# design.net
KiCad netlist of a schematic drawn in Altium Designer
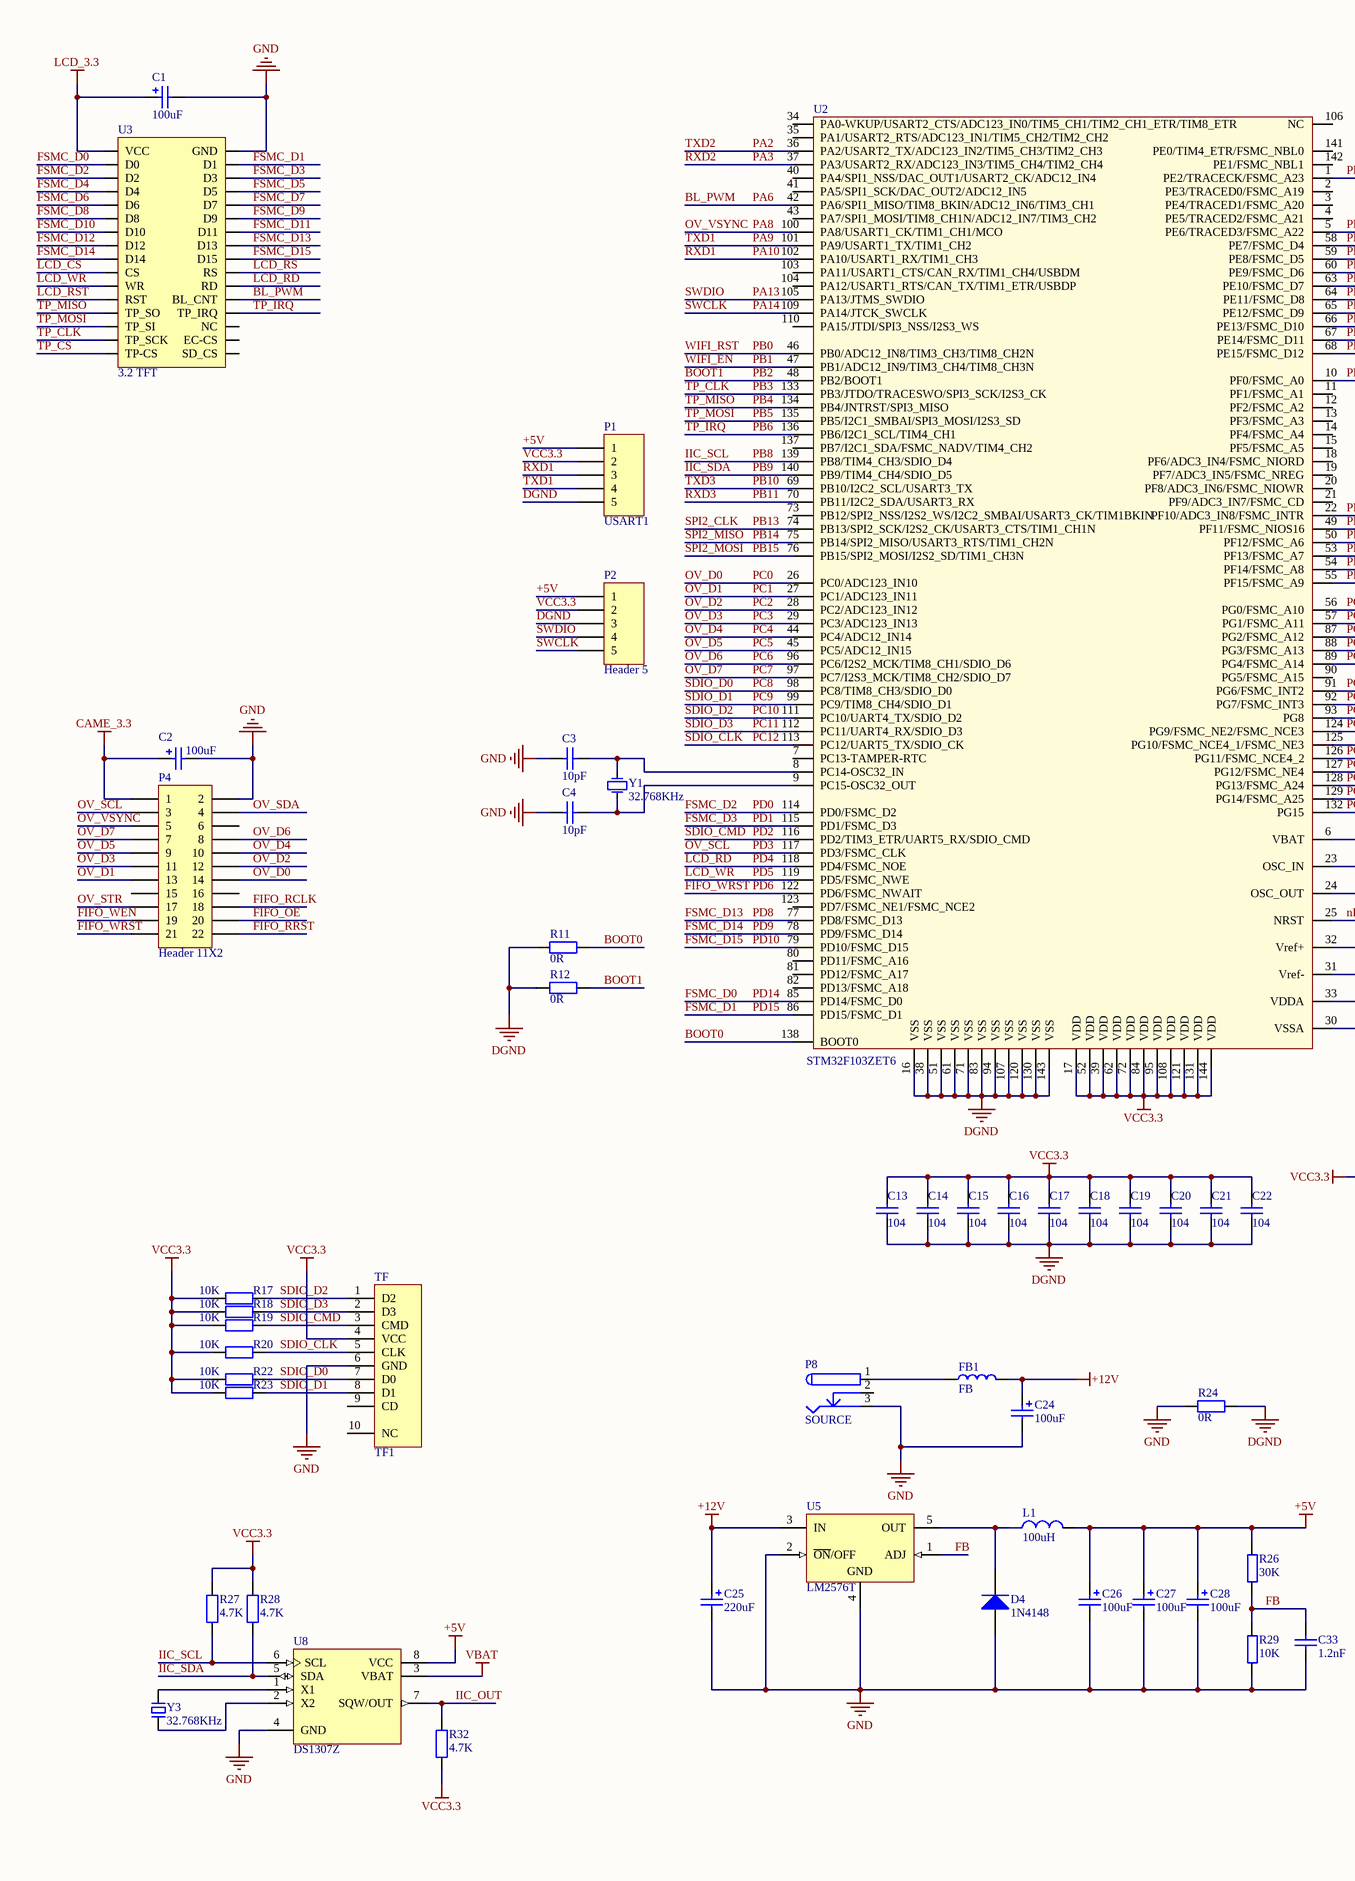
[diagram p0: 无线门禁系统.SchDoc, left]
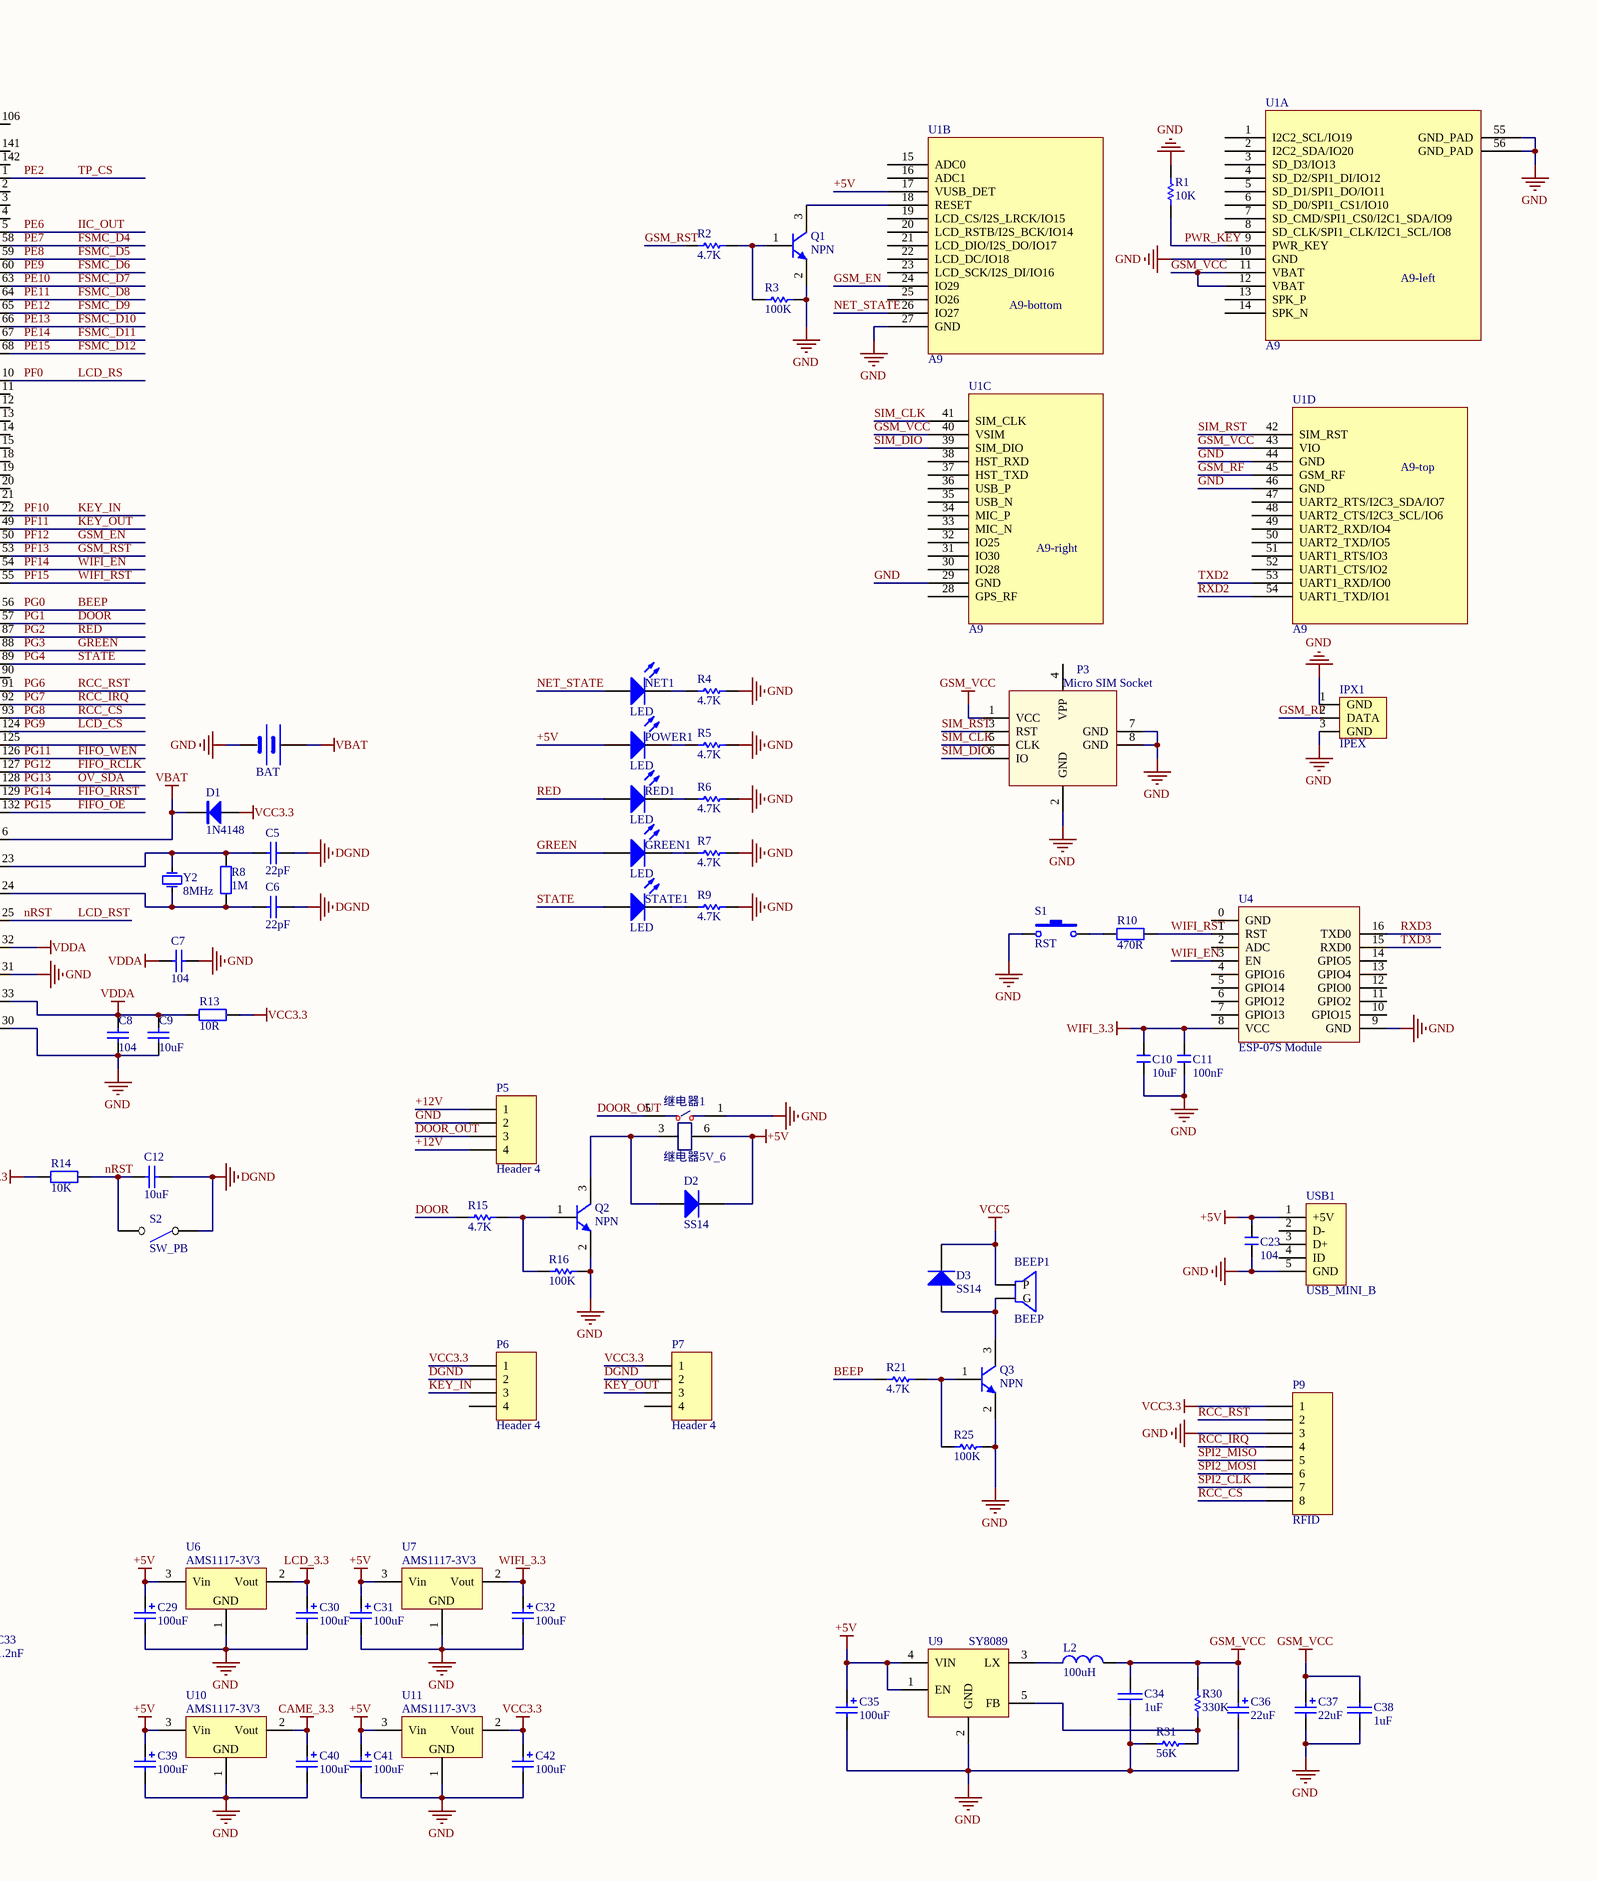
[diagram p1: 无线门禁系统.SchDoc, right]

(export (version "E")
  (design (tool "Eeschema 10.0.6"))
  (components
    (comp (ref "BAT")
      (value "BATT")
      (footprint "MyLib:纽扣电池座CR1220")
      (libsource (lib "Peace的集成库") (part "BAT"))
    )
    (comp (ref "BEEP1") (value "BEEP") (footprint "MyLib:BUZZER") (libsource (lib "门禁系统") (part "BEEP")))
    (comp (ref "C1")
      (value "100uF")
      (footprint "WiFi无线门禁_主机:CAP_TAN_B_3518")
      (description "Polarized Capacitor (Radial)")
      (fields
        (field (name "VOLTAGE") "16V")
        (field (name "Comment") "Cap Pol SMT D")
        (field (name "PUBLISHER") "Altium Limited")
      )
      (libsource (lib "MyLib") (part "Cap Pol SMT D"))
    )
    (comp (ref "C2")
      (value "100uF")
      (footprint "WiFi无线门禁_主机:CAP_TAN_B_3518")
      (description "Polarized Capacitor (Radial)")
      (fields
        (field (name "VOLTAGE") "16V")
        (field (name "Comment") "Cap Pol SMT D")
        (field (name "PUBLISHER") "Altium Limited")
      )
      (libsource (lib "MyLib") (part "Cap Pol SMT D"))
    )
    (comp (ref "C3")
      (value "10pF")
      (footprint "MyLib:0805_c")
      (description "Capacitor")
      (fields (field (name "Comment") "Cap1") (field (name "PUBLISHER") "Altium Limited"))
      (libsource (lib "Peace的集成库") (part "Cap1"))
    )
    (comp (ref "C4")
      (value "10pF")
      (footprint "MyLib:0805_c")
      (description "Capacitor")
      (fields (field (name "Comment") "Cap1") (field (name "PUBLISHER") "Altium Limited"))
      (libsource (lib "Peace的集成库") (part "Cap1"))
    )
    (comp (ref "C5")
      (value "22pF")
      (footprint "MyLib:0805_c")
      (description "Capacitor")
      (fields (field (name "Comment") "Cap1") (field (name "PUBLISHER") "Altium Limited"))
      (libsource (lib "Peace的集成库") (part "Cap1"))
    )
    (comp (ref "C6")
      (value "22pF")
      (footprint "MyLib:0805_c")
      (description "Capacitor")
      (fields (field (name "Comment") "Cap1") (field (name "PUBLISHER") "Altium Limited"))
      (libsource (lib "Peace的集成库") (part "Cap1"))
    )
    (comp (ref "C7")
      (value "104")
      (footprint "MyLib:0805_c")
      (description "Capacitor")
      (fields (field (name "Comment") "Cap1") (field (name "PUBLISHER") "Altium Limited"))
      (libsource (lib "Peace的集成库") (part "Cap1"))
    )
    (comp (ref "C8")
      (value "104")
      (footprint "MyLib:0805_c")
      (description "Capacitor")
      (fields (field (name "Comment") "Cap1") (field (name "PUBLISHER") "Altium Limited"))
      (libsource (lib "Peace的集成库") (part "Cap1"))
    )
    (comp (ref "C9")
      (value "10uF")
      (footprint "MyLib:0805_c")
      (description "Capacitor")
      (fields (field (name "Comment") "Cap1") (field (name "PUBLISHER") "Altium Limited"))
      (libsource (lib "Peace的集成库") (part "Cap1"))
    )
    (comp (ref "C10")
      (value "10uF")
      (footprint "MyLib:0805_c")
      (description "无极性贴片电容")
      (fields (field (name "版权归属") "源创客"))
      (libsource (lib "EEBANG_STM32F103ZET6") (part "C"))
    )
    (comp (ref "C11")
      (value "100nF")
      (footprint "MyLib:0805_c")
      (description "无极性贴片电容")
      (fields (field (name "版权归属") "源创客"))
      (libsource (lib "EEBANG_STM32F103ZET6") (part "C"))
    )
    (comp (ref "C12")
      (value "10uF")
      (footprint "MyLib:0805_c")
      (description "Capacitor")
      (fields (field (name "Comment") "Cap1") (field (name "PUBLISHER") "Altium Limited"))
      (libsource (lib "Peace的集成库") (part "Cap1"))
    )
    (comp (ref "C13")
      (value "104")
      (footprint "MyLib:0805_c")
      (description "Capacitor")
      (fields (field (name "Comment") "Cap1") (field (name "PUBLISHER") "Altium Limited"))
      (libsource (lib "Peace的集成库") (part "Cap1"))
    )
    (comp (ref "C14")
      (value "104")
      (footprint "MyLib:0805_c")
      (description "Capacitor")
      (fields (field (name "Comment") "Cap1") (field (name "PUBLISHER") "Altium Limited"))
      (libsource (lib "Peace的集成库") (part "Cap1"))
    )
    (comp (ref "C15")
      (value "104")
      (footprint "MyLib:0805_c")
      (description "Capacitor")
      (fields (field (name "Comment") "Cap1") (field (name "PUBLISHER") "Altium Limited"))
      (libsource (lib "Peace的集成库") (part "Cap1"))
    )
    (comp (ref "C16")
      (value "104")
      (footprint "MyLib:0805_c")
      (description "Capacitor")
      (fields (field (name "Comment") "Cap1") (field (name "PUBLISHER") "Altium Limited"))
      (libsource (lib "Peace的集成库") (part "Cap1"))
    )
    (comp (ref "C17")
      (value "104")
      (footprint "MyLib:0805_c")
      (description "Capacitor")
      (fields (field (name "Comment") "Cap1") (field (name "PUBLISHER") "Altium Limited"))
      (libsource (lib "Peace的集成库") (part "Cap1"))
    )
    (comp (ref "C18")
      (value "104")
      (footprint "MyLib:0805_c")
      (description "Capacitor")
      (fields (field (name "Comment") "Cap1") (field (name "PUBLISHER") "Altium Limited"))
      (libsource (lib "Peace的集成库") (part "Cap1"))
    )
    (comp (ref "C19")
      (value "104")
      (footprint "MyLib:0805_c")
      (description "Capacitor")
      (fields (field (name "Comment") "Cap1") (field (name "PUBLISHER") "Altium Limited"))
      (libsource (lib "Peace的集成库") (part "Cap1"))
    )
    (comp (ref "C20")
      (value "104")
      (footprint "MyLib:0805_c")
      (description "Capacitor")
      (fields (field (name "Comment") "Cap1") (field (name "PUBLISHER") "Altium Limited"))
      (libsource (lib "Peace的集成库") (part "Cap1"))
    )
    (comp (ref "C21")
      (value "104")
      (footprint "MyLib:0805_c")
      (description "Capacitor")
      (fields (field (name "Comment") "Cap1") (field (name "PUBLISHER") "Altium Limited"))
      (libsource (lib "Peace的集成库") (part "Cap1"))
    )
    (comp (ref "C22")
      (value "104")
      (footprint "MyLib:0805_c")
      (description "Capacitor")
      (fields (field (name "Comment") "Cap1") (field (name "PUBLISHER") "Altium Limited"))
      (libsource (lib "Peace的集成库") (part "Cap1"))
    )
    (comp (ref "C23")
      (value "104")
      (footprint "MyLib:0805_c")
      (description "无极性贴片电容")
      (fields (field (name "版权归属") "源创客"))
      (libsource (lib "EEBANG_STM32F103ZET6") (part "C"))
    )
    (comp (ref "C24")
      (value "100uF")
      (footprint "WiFi无线门禁_主机:CAP_TAN_B_3518")
      (description "Polarized Capacitor (Radial)")
      (fields
        (field (name "VOLTAGE") "16V")
        (field (name "Comment") "Cap Tan A")
        (field (name "PUBLISHER") "Altium Limited")
      )
      (libsource (lib "MyLib") (part "Cap Tan A"))
    )
    (comp (ref "C25")
      (value "220uF")
      (footprint "WiFi无线门禁_主机:CAP_TAN_B_3518")
      (description "Polarized Capacitor (Radial)")
      (fields (field (name "Comment") "Cap Electrolytic") (field (name "PUBLISHER") "Altium Limited"))
      (libsource (lib "MyLib") (part "Cap Electrolytic"))
    )
    (comp (ref "C26")
      (value "100uF")
      (footprint "WiFi无线门禁_主机:CAP_TAN_B_3518")
      (description "Polarized Capacitor (Radial)")
      (fields
        (field (name "VOLTAGE") "16V")
        (field (name "Comment") "Cap Tan A")
        (field (name "PUBLISHER") "Altium Limited")
      )
      (libsource (lib "MyLib") (part "Cap Tan A"))
    )
    (comp (ref "C27")
      (value "100uF")
      (footprint "WiFi无线门禁_主机:CAP_TAN_B_3518")
      (description "Polarized Capacitor (Radial)")
      (fields
        (field (name "VOLTAGE") "16V")
        (field (name "Comment") "Cap Tan A")
        (field (name "PUBLISHER") "Altium Limited")
      )
      (libsource (lib "MyLib") (part "Cap Tan A"))
    )
    (comp (ref "C28")
      (value "100uF")
      (footprint "WiFi无线门禁_主机:CAP_TAN_B_3518")
      (description "Polarized Capacitor (Radial)")
      (fields
        (field (name "VOLTAGE") "16V")
        (field (name "Comment") "Cap Tan A")
        (field (name "PUBLISHER") "Altium Limited")
      )
      (libsource (lib "MyLib") (part "Cap Tan A"))
    )
    (comp (ref "C29")
      (value "100uF")
      (footprint "WiFi无线门禁_主机:CAP_TAN_B_3518")
      (description "Polarized Capacitor (Radial)")
      (fields
        (field (name "VOLTAGE") "16V")
        (field (name "Comment") "Cap Pol SMT D")
        (field (name "PUBLISHER") "Altium Limited")
      )
      (libsource (lib "MyLib") (part "Cap Pol SMT D"))
    )
    (comp (ref "C30")
      (value "100uF")
      (footprint "WiFi无线门禁_主机:CAP_TAN_B_3518")
      (description "Polarized Capacitor (Radial)")
      (fields
        (field (name "VOLTAGE") "16V")
        (field (name "Comment") "Cap Pol SMT D")
        (field (name "PUBLISHER") "Altium Limited")
      )
      (libsource (lib "MyLib") (part "Cap Pol SMT D"))
    )
    (comp (ref "C31")
      (value "100uF")
      (footprint "WiFi无线门禁_主机:CAP_TAN_B_3518")
      (description "Polarized Capacitor (Radial)")
      (fields
        (field (name "VOLTAGE") "16V")
        (field (name "Comment") "Cap Pol SMT D")
        (field (name "PUBLISHER") "Altium Limited")
      )
      (libsource (lib "MyLib") (part "Cap Pol SMT D"))
    )
    (comp (ref "C32")
      (value "100uF")
      (footprint "WiFi无线门禁_主机:CAP_TAN_B_3518")
      (description "Polarized Capacitor (Radial)")
      (fields
        (field (name "VOLTAGE") "16V")
        (field (name "Comment") "Cap Pol SMT D")
        (field (name "PUBLISHER") "Altium Limited")
      )
      (libsource (lib "MyLib") (part "Cap Pol SMT D"))
    )
    (comp (ref "C33")
      (value "1.2nF")
      (footprint "MyLib:0805_c")
      (description "Polarized Capacitor (Radial)")
      (fields (field (name "Comment") "Cap Chip 0805") (field (name "PUBLISHER") "Altium Limited"))
      (libsource (lib "MyLib") (part "Cap Chip 0805"))
    )
    (comp (ref "C34") (value "1uF") (footprint "MyLib:0805_c") (libsource (lib "MyLib") (part "CAP")))
    (comp (ref "C35")
      (value "100uF")
      (footprint "WiFi无线门禁_主机:CAP_TAN_B_3518")
      (description "Polarized Capacitor (Radial)")
      (fields
        (field (name "VOLTAGE") "16V")
        (field (name "Comment") "Cap Pol SMT D")
        (field (name "PUBLISHER") "Altium Limited")
      )
      (libsource (lib "MyLib") (part "Cap Pol SMT D"))
    )
    (comp (ref "C36")
      (value "22uF")
      (footprint "WiFi无线门禁_主机:CAP_TAN_B_3518")
      (description "Polarized Capacitor (Radial)")
      (fields
        (field (name "VOLTAGE") "16V")
        (field (name "Comment") "Cap Pol SMT D")
        (field (name "PUBLISHER") "Altium Limited")
      )
      (libsource (lib "MyLib") (part "Cap Pol SMT D"))
    )
    (comp (ref "C37")
      (value "22uF")
      (footprint "WiFi无线门禁_主机:CAP_TAN_B_3518")
      (description "Polarized Capacitor (Radial)")
      (fields
        (field (name "VOLTAGE") "16V")
        (field (name "Comment") "Cap Pol SMT D")
        (field (name "PUBLISHER") "Altium Limited")
      )
      (libsource (lib "MyLib") (part "Cap Pol SMT D"))
    )
    (comp (ref "C38") (value "1uF") (footprint "MyLib:0805_c") (libsource (lib "MyLib") (part "CAP")))
    (comp (ref "C39")
      (value "100uF")
      (footprint "WiFi无线门禁_主机:CAP_TAN_B_3518")
      (description "Polarized Capacitor (Radial)")
      (fields
        (field (name "VOLTAGE") "16V")
        (field (name "Comment") "Cap Pol SMT D")
        (field (name "PUBLISHER") "Altium Limited")
      )
      (libsource (lib "MyLib") (part "Cap Pol SMT D"))
    )
    (comp (ref "C40")
      (value "100uF")
      (footprint "WiFi无线门禁_主机:CAP_TAN_B_3518")
      (description "Polarized Capacitor (Radial)")
      (fields
        (field (name "VOLTAGE") "16V")
        (field (name "Comment") "Cap Pol SMT D")
        (field (name "PUBLISHER") "Altium Limited")
      )
      (libsource (lib "MyLib") (part "Cap Pol SMT D"))
    )
    (comp (ref "C41")
      (value "100uF")
      (footprint "WiFi无线门禁_主机:CAP_TAN_B_3518")
      (description "Polarized Capacitor (Radial)")
      (fields
        (field (name "VOLTAGE") "16V")
        (field (name "Comment") "Cap Pol SMT D")
        (field (name "PUBLISHER") "Altium Limited")
      )
      (libsource (lib "MyLib") (part "Cap Pol SMT D"))
    )
    (comp (ref "C42")
      (value "100uF")
      (footprint "WiFi无线门禁_主机:CAP_TAN_B_3518")
      (description "Polarized Capacitor (Radial)")
      (fields
        (field (name "VOLTAGE") "16V")
        (field (name "Comment") "Cap Pol SMT D")
        (field (name "PUBLISHER") "Altium Limited")
      )
      (libsource (lib "MyLib") (part "Cap Pol SMT D"))
    )
    (comp (ref "D1")
      (value "1N4148")
      (footprint "二极管:DIODE SMC")
      (description "高速开关二极管")
      (fields (field (name "版权归属") "源创客"))
      (libsource (lib "EEBANG_STM32F103ZET6") (part "1N4148"))
    )
    (comp (ref "D2")
      (value "SS14")
      (footprint "二极管:DIODE SMC")
      (description "High Conductance Fast Diode")
      (fields (field (name "PUBLISHER") "Altium Limited"))
      (libsource (lib "My Footprint") (part "1N4148"))
    )
    (comp (ref "D3")
      (value "SS14")
      (footprint "二极管:DIODE SMC")
      (description "High Conductance Fast Diode")
      (fields (field (name "PUBLISHER") "Altium Limited"))
      (libsource (lib "My Footprint") (part "1N4148"))
    )
    (comp (ref "D4")
      (value "1N4148")
      (footprint "二极管:DIODE SMC")
      (description "3 Amp Medium Power Silicon Rectifier Diode")
      (fields (field (name "PUBLISHER") "Altium Limited"))
      (libsource (lib "MyLib") (part "Diode"))
    )
    (comp (ref "FB1")
      (value "FB")
      (footprint "MyLib:FU 1206")
      (description "磁珠")
      (libsource (lib "My Footprint") (part "FB"))
    )
    (comp (ref "GREEN1") (value "LED") (footprint "MyLib:0805_LED") (libsource (lib "MyLib") (part "LED")))
    (comp (ref "IPX1")
      (value "IPEX")
      (footprint "IPEX")
      (description "IPEX座")
      (libsource (lib "PCB_Project1") (part "IPEX"))
    )
    (comp (ref "L1") (value "100uH") (footprint "MyLib:L_3") (libsource (lib "MyLib") (part "inductance")))
    (comp (ref "L2") (value "100uH") (footprint "MyLib:L_3") (libsource (lib "MyLib") (part "inductance")))
    (comp (ref "NET1") (value "LED") (footprint "MyLib:0805_LED") (libsource (lib "MyLib") (part "LED")))
    (comp (ref "P1")
      (value "USART1")
      (footprint "MyLib:HX2.54-5")
      (description "Header, 5-Pin")
      (fields (field (name "PUBLISHER") "Altium Limited"))
      (libsource (lib "MyLib") (part "Header 5"))
    )
    (comp (ref "P2")
      (value "Header 5")
      (footprint "MyLib:HX2.54-5")
      (description "Header, 5-Pin")
      (fields (field (name "PUBLISHER") "Altium Limited"))
      (libsource (lib "MyLib") (part "Header 5"))
    )
    (comp (ref "P3")
      (value "Micro SIM Socket")
      (footprint "PCB_Project1:SIM_micro")
      (libsource (lib "MyLib") (part "Micro SIM"))
    )
    (comp (ref "P4")
      (value "Header 11X2")
      (footprint "HDR2X11")
      (description "Header, 11-Pin, Dual row")
      (fields (field (name "PUBLISHER") "Altium Limited"))
      (libsource (lib "MyLib") (part "Header 11X2"))
    )
    (comp (ref "P5")
      (value "Header 4")
      (footprint "MyLib:HX2.54-4")
      (description "Header, 4-Pin")
      (fields (field (name "PUBLISHER") "Altium Limited"))
      (libsource (lib "MyLib") (part "Header 4"))
    )
    (comp (ref "P6")
      (value "Header 4")
      (footprint "MyLib:HX2.54-4")
      (description "Header, 4-Pin")
      (fields (field (name "PUBLISHER") "Altium Limited"))
      (libsource (lib "MyLib") (part "Header 4"))
    )
    (comp (ref "P7")
      (value "Header 4")
      (footprint "MyLib:HX2.54-4")
      (description "Header, 4-Pin")
      (fields (field (name "PUBLISHER") "Altium Limited"))
      (libsource (lib "MyLib") (part "Header 4"))
    )
    (comp (ref "P8")
      (value "SOURCE")
      (footprint "MyLib:source")
      (fields (field (name "PUBLISHER") "Altium Limited"))
      (libsource (lib "My Footprint") (part "SOURCE"))
    )
    (comp (ref "P9")
      (value "RFID")
      (footprint "MyLib:HX2.54-8")
      (description "Header, 8-Pin")
      (fields (field (name "PUBLISHER") "Altium Limited"))
      (libsource (lib "MyLib") (part "Header 8"))
    )
    (comp (ref "POWER1") (value "LED") (footprint "MyLib:0805_LED") (libsource (lib "MyLib") (part "LED")))
    (comp (ref "Q1")
      (value "NPN")
      (footprint "MyLib:SOT-23-3")
      (description "贴片")
      (libsource (lib "My Footprint") (part "NPN2"))
    )
    (comp (ref "Q2")
      (value "NPN")
      (footprint "MyLib:SOT-23-3")
      (description "贴片")
      (libsource (lib "My Footprint") (part "NPN2"))
    )
    (comp (ref "Q3")
      (value "NPN")
      (footprint "MyLib:SOT-23-3")
      (description "贴片")
      (libsource (lib "My Footprint") (part "NPN2"))
    )
    (comp (ref "R1")
      (value "10K")
      (footprint "0805_r")
      (description "Resistor")
      (fields (field (name "PUBLISHER") "Altium Limited"))
      (libsource (lib "My Footprint") (part "RES"))
    )
    (comp (ref "R2")
      (value "4.7K")
      (footprint "0805_r")
      (description "Resistor")
      (fields (field (name "PUBLISHER") "Altium Limited"))
      (libsource (lib "My Footprint") (part "RES"))
    )
    (comp (ref "R3")
      (value "100K")
      (footprint "0805_r")
      (description "Resistor")
      (fields (field (name "PUBLISHER") "Altium Limited"))
      (libsource (lib "My Footprint") (part "RES"))
    )
    (comp (ref "R4")
      (value "4.7K")
      (footprint "0805_r")
      (description "Resistor")
      (fields (field (name "PUBLISHER") "Altium Limited"))
      (libsource (lib "My Footprint") (part "RES"))
    )
    (comp (ref "R5")
      (value "4.7K")
      (footprint "0805_r")
      (description "Resistor")
      (fields (field (name "PUBLISHER") "Altium Limited"))
      (libsource (lib "My Footprint") (part "RES"))
    )
    (comp (ref "R6")
      (value "4.7K")
      (footprint "0805_r")
      (description "Resistor")
      (fields (field (name "PUBLISHER") "Altium Limited"))
      (libsource (lib "My Footprint") (part "RES"))
    )
    (comp (ref "R7")
      (value "4.7K")
      (footprint "0805_r")
      (description "Resistor")
      (fields (field (name "PUBLISHER") "Altium Limited"))
      (libsource (lib "My Footprint") (part "RES"))
    )
    (comp (ref "R8")
      (value "1M")
      (footprint "MyLib:0805_r")
      (description "Resistor")
      (fields (field (name "Comment") "Res1") (field (name "PUBLISHER") "Altium Limited"))
      (libsource (lib "") (part "Res1_2"))
    )
    (comp (ref "R9")
      (value "4.7K")
      (footprint "0805_r")
      (description "Resistor")
      (fields (field (name "PUBLISHER") "Altium Limited"))
      (libsource (lib "My Footprint") (part "RES"))
    )
    (comp (ref "R10")
      (value "470R")
      (footprint "MyLib:0805_r")
      (description "Resistor")
      (fields (field (name "Comment") "Res1") (field (name "PUBLISHER") "Altium Limited"))
      (libsource (lib "Peace的集成库") (part "Res1"))
    )
    (comp (ref "R11")
      (value "0R")
      (footprint "MyLib:0805_r")
      (description "Resistor")
      (fields (field (name "Comment") "Res1") (field (name "PUBLISHER") "Altium Limited"))
      (libsource (lib "Peace的集成库") (part "Res1"))
    )
    (comp (ref "R12")
      (value "0R")
      (footprint "MyLib:0805_r")
      (description "Resistor")
      (fields (field (name "Comment") "Res1") (field (name "PUBLISHER") "Altium Limited"))
      (libsource (lib "Peace的集成库") (part "Res1"))
    )
    (comp (ref "R13")
      (value "10R")
      (footprint "MyLib:0805_r")
      (description "Resistor")
      (fields (field (name "Comment") "Res1") (field (name "PUBLISHER") "Altium Limited"))
      (libsource (lib "") (part "Res1_1"))
    )
    (comp (ref "R14")
      (value "10K")
      (footprint "MyLib:0805_r")
      (description "Resistor")
      (fields (field (name "Comment") "Res1") (field (name "PUBLISHER") "Altium Limited"))
      (libsource (lib "Peace的集成库") (part "Res1"))
    )
    (comp (ref "R15")
      (value "4.7K")
      (footprint "0805_r")
      (description "Resistor")
      (fields (field (name "PUBLISHER") "Altium Limited"))
      (libsource (lib "My Footprint") (part "RES"))
    )
    (comp (ref "R16")
      (value "100K")
      (footprint "0805_r")
      (description "Resistor")
      (fields (field (name "PUBLISHER") "Altium Limited"))
      (libsource (lib "My Footprint") (part "RES"))
    )
    (comp (ref "R17")
      (value "10K")
      (footprint "0805_r")
      (description "贴片电阻")
      (fields (field (name "版权归属") "源创客"))
      (libsource (lib "EEBANG_STM32F103ZET6") (part "R"))
    )
    (comp (ref "R18")
      (value "10K")
      (footprint "0805_r")
      (description "贴片电阻")
      (fields (field (name "版权归属") "源创客"))
      (libsource (lib "EEBANG_STM32F103ZET6") (part "R"))
    )
    (comp (ref "R19")
      (value "10K")
      (footprint "0805_r")
      (description "贴片电阻")
      (fields (field (name "版权归属") "源创客"))
      (libsource (lib "EEBANG_STM32F103ZET6") (part "R"))
    )
    (comp (ref "R20")
      (value "10K")
      (footprint "0805_r")
      (description "贴片电阻")
      (fields (field (name "版权归属") "源创客"))
      (libsource (lib "EEBANG_STM32F103ZET6") (part "R"))
    )
    (comp (ref "R21")
      (value "4.7K")
      (footprint "0805_r")
      (description "Resistor")
      (fields (field (name "PUBLISHER") "Altium Limited"))
      (libsource (lib "My Footprint") (part "RES"))
    )
    (comp (ref "R22")
      (value "10K")
      (footprint "0805_r")
      (description "贴片电阻")
      (fields (field (name "版权归属") "源创客"))
      (libsource (lib "EEBANG_STM32F103ZET6") (part "R"))
    )
    (comp (ref "R23")
      (value "10K")
      (footprint "0805_r")
      (description "贴片电阻")
      (fields (field (name "版权归属") "源创客"))
      (libsource (lib "EEBANG_STM32F103ZET6") (part "R"))
    )
    (comp (ref "R24")
      (value "0R")
      (footprint "MyLib:0805_r")
      (description "Resistor")
      (fields (field (name "Comment") "Res1") (field (name "PUBLISHER") "Altium Limited"))
      (libsource (lib "Peace的集成库") (part "Res1"))
    )
    (comp (ref "R25")
      (value "100K")
      (footprint "0805_r")
      (description "Resistor")
      (fields (field (name "PUBLISHER") "Altium Limited"))
      (libsource (lib "My Footprint") (part "RES"))
    )
    (comp (ref "R26") (value "30K") (footprint "MyLib:0805_r") (libsource (lib "MyLib") (part "RES3")))
    (comp (ref "R27")
      (value "4.7K")
      (footprint "0805_r")
      (description "贴片电阻")
      (fields (field (name "版权归属") "源创客"))
      (libsource (lib "EEBANG_STM32F103ZET6") (part "R"))
    )
    (comp (ref "R28")
      (value "4.7K")
      (footprint "0805_r")
      (description "贴片电阻")
      (fields (field (name "版权归属") "源创客"))
      (libsource (lib "EEBANG_STM32F103ZET6") (part "R"))
    )
    (comp (ref "R29") (value "10K") (footprint "0805_r") (libsource (lib "MyLib") (part "RES3")))
    (comp (ref "R30")
      (value "330K")
      (footprint "0805_r")
      (description "Resistor")
      (fields (field (name "PUBLISHER") "Altium Limited"))
      (libsource (lib "My Footprint") (part "RES"))
    )
    (comp (ref "R31")
      (value "56K")
      (footprint "0805_r")
      (description "Resistor")
      (fields (field (name "PUBLISHER") "Altium Limited"))
      (libsource (lib "My Footprint") (part "RES"))
    )
    (comp (ref "R32")
      (value "4.7K")
      (footprint "0805_r")
      (description "贴片电阻")
      (fields (field (name "版权归属") "源创客"))
      (libsource (lib "EEBANG_STM32F103ZET6") (part "R"))
    )
    (comp (ref "RED1") (value "LED") (footprint "MyLib:0805_LED") (libsource (lib "MyLib") (part "LED")))
    (comp (ref "S1")
      (value "RST")
      (footprint "KEY_2")
      (description "Switch")
      (fields (field (name "PUBLISHER") "Altium Limited"))
      (libsource (lib "Peace的集成库") (part "SW-PB"))
    )
    (comp (ref "S2") (value "SW_PB") (footprint "MyLib:KEY_2") (libsource (lib "MyLib") (part "单刀开关")))
    (comp (ref "STATE1") (value "LED") (footprint "MyLib:0805_LED") (libsource (lib "MyLib") (part "LED")))
    (comp (ref "TF1") (value "TF") (footprint "TF-2") (libsource (lib "WiFi无线门禁_主机") (part "TF2")))
    (comp (ref "U1") (value "A9") (footprint "A9") (libsource (lib "A9") (part "A9")))
    (comp (ref "U2")
      (value "STM32F103ZET6")
      (footprint "MyLib:TQFP144_L")
      (libsource (lib "EEBANG_STM32F103ZET6") (part "STM32F103ZET6"))
    )
    (comp (ref "U3") (value "3.2 TFT") (footprint "LCD3.2") (libsource (lib "WiFi无线门禁_主机") (part "LCD3.2")))
    (comp (ref "U4")
      (value "ESP-07S Module")
      (footprint "ESP-07S Module")
      (libsource (lib "ESP-07S Module") (part "ESP-07S Module"))
    )
    (comp (ref "U5")
      (value "LM2576T")
      (footprint "MyLib:TO-263-5")
      (description "Negative Low Dropout Adjustable Regulator")
      (fields
        (field (name "PARTNUMBER") "LM2991T")
        (field (name "MANUFACTURER") "National Semiconductor")
        (field (name "PUBLISHER") "Altium Limited")
      )
      (libsource (lib "MyLib") (part "LM2576T"))
    )
    (comp (ref "U6")
      (value "AMS1117-3V3")
      (footprint "MyLib:SOT-223")
      (description "三端稳压芯片")
      (fields (field (name "版权归属") "源创客"))
      (libsource (lib "EEBANG_STM32F103ZET6") (part "AMS1117"))
    )
    (comp (ref "U7")
      (value "AMS1117-3V3")
      (footprint "MyLib:SOT-223")
      (description "三端稳压芯片")
      (fields (field (name "版权归属") "源创客"))
      (libsource (lib "EEBANG_STM32F103ZET6") (part "AMS1117"))
    )
    (comp (ref "U8")
      (value "DS1307Z")
      (footprint "SOIC8_L")
      (description "64 X 8 Serial Real-Time Clock")
      (fields (field (name "PUBLISHER") "Altium Limited"))
      (libsource (lib "WiFi无线门禁_主机") (part "DS1307Z"))
    )
    (comp (ref "U9") (value "SY8089") (footprint "MyLib:SOP-5N") (libsource (lib "MyLib") (part "RT8059")))
    (comp (ref "U10")
      (value "AMS1117-3V3")
      (footprint "MyLib:SOT-223")
      (description "三端稳压芯片")
      (fields (field (name "版权归属") "源创客"))
      (libsource (lib "EEBANG_STM32F103ZET6") (part "AMS1117"))
    )
    (comp (ref "U11")
      (value "AMS1117-3V3")
      (footprint "MyLib:SOT-223")
      (description "三端稳压芯片")
      (fields (field (name "版权归属") "源创客"))
      (libsource (lib "EEBANG_STM32F103ZET6") (part "AMS1117"))
    )
    (comp (ref "USB1")
      (value "USB_MINI_B")
      (footprint "USB-MICRO_B")
      (description "微型USB母座")
      (fields (field (name "版权归属") "源创客"))
      (libsource (lib "EEBANG_STM32F103ZET6") (part "USB-5P"))
    )
    (comp (ref "Y1")
      (value "32.768KHz")
      (footprint "MyLib:XTAL-2")
      (description "Crystal Oscillator")
      (fields (field (name "PUBLISHER") "Altium Limited"))
      (libsource (lib "Peace的集成库") (part "XTAL"))
    )
    (comp (ref "Y2")
      (value "8MHz")
      (footprint "EEBANG_STM32F103ZET6:XTAL-49S SMD - L")
      (description "Crystal Oscillator")
      (fields (field (name "PUBLISHER") "Altium Limited"))
      (libsource (lib "Peace的集成库") (part "XTAL"))
    )
    (comp (ref "Y3")
      (value "32.768KHz")
      (footprint "XTAL-2")
      (description "2脚晶振")
      (fields (field (name "版权归属") "源创客"))
      (libsource (lib "EEBANG_STM32F103ZET6") (part "XTAL-2"))
    )
    (comp (ref "继电器1") (value "继电器5V_6") (footprint "门禁系统:继电器5V_6") (libsource (lib "门禁系统") (part "继电器5V_6")))
  )
  (nets
    (net (code "1") (name "+5V") (class "Default")
      (node (ref "C23") (pin "2") (pinfunction "2_2") (pintype "passive"))
      (node (ref "C26") (pin "2") (pinfunction "1_2") (pintype "passive"))
      (node (ref "C27") (pin "2") (pinfunction "1_2") (pintype "passive"))
      (node (ref "C28") (pin "2") (pinfunction "1_2") (pintype "passive"))
      (node (ref "C29") (pin "1") (pinfunction "1_1") (pintype "passive"))
      (node (ref "C31") (pin "1") (pinfunction "1_1") (pintype "passive"))
      (node (ref "C35") (pin "1") (pinfunction "1_1") (pintype "passive"))
      (node (ref "C39") (pin "1") (pinfunction "1_1") (pintype "passive"))
      (node (ref "C41") (pin "1") (pinfunction "1_1") (pintype "passive"))
      (node (ref "D2") (pin "2") (pinfunction "K_2") (pintype "passive"))
      (node (ref "L1") (pin "1") (pinfunction "1_1") (pintype "passive"))
      (node (ref "P1") (pin "1") (pinfunction "1_1") (pintype "passive"))
      (node (ref "P2") (pin "1") (pinfunction "1_1") (pintype "passive"))
      (node (ref "POWER1") (pin "1") (pinfunction "A_1") (pintype "passive"))
      (node (ref "R26") (pin "2") (pintype "passive"))
      (node (ref "U1") (pin "17") (pinfunction "VUSB_DET_17") (pintype "passive"))
      (node (ref "U10") (pin "3") (pinfunction "Vin_3") (pintype "passive"))
      (node (ref "U11") (pin "3") (pinfunction "Vin_3") (pintype "passive"))
      (node (ref "U6") (pin "3") (pinfunction "Vin_3") (pintype "passive"))
      (node (ref "U7") (pin "3") (pinfunction "Vin_3") (pintype "passive"))
      (node (ref "U8") (pin "8") (pinfunction "VCC_8") (pintype "power_in"))
      (node (ref "U9") (pin "1") (pinfunction "EN_1") (pintype "passive"))
      (node (ref "U9") (pin "4") (pinfunction "VIN_4") (pintype "passive"))
      (node (ref "USB1") (pin "1") (pinfunction "+5V_1") (pintype "passive"))
      (node (ref "继电器1") (pin "6") (pinfunction "FLA_6") (pintype "passive"))
    )
    (net (code "2") (name "+12V") (class "Default")
      (node (ref "C24") (pin "2") (pinfunction "1_2") (pintype "passive"))
      (node (ref "C25") (pin "1") (pinfunction "1_1") (pintype "passive"))
      (node (ref "FB1") (pin "2") (pinfunction "2_2") (pintype "passive"))
      (node (ref "P5") (pin "1") (pinfunction "1_1") (pintype "passive"))
      (node (ref "P5") (pin "4") (pinfunction "4_4") (pintype "passive"))
      (node (ref "U5") (pin "3") (pinfunction "IN_3") (pintype "power_in"))
    )
    (net (code "3") (name "/BEEP") (class "Default")
      (node (ref "R21") (pin "1") (pinfunction "1_1") (pintype "passive"))
      (node (ref "U2") (pin "56") (pinfunction "PG0/FSMC_A10_56") (pintype "passive"))
    )
    (net (code "4") (name "/BL_PWM") (class "Default")
      (node (ref "U2") (pin "42") (pinfunction "PA6/SPI1_MISO/TIM8_BKIN/ADC12_IN6/TIM3_CH1_42") (pintype "passive"))
      (node (ref "U3") (pin "24") (pinfunction "BL_CNT_24") (pintype "passive"))
    )
    (net (code "5") (name "/BOOT0") (class "Default")
      (node (ref "R11") (pin "1") (pinfunction "1_1") (pintype "passive"))
      (node (ref "U2") (pin "138") (pinfunction "BOOT0_138") (pintype "passive"))
    )
    (net (code "6") (name "/BOOT1") (class "Default")
      (node (ref "R12") (pin "1") (pinfunction "1_1") (pintype "passive"))
      (node (ref "U2") (pin "48") (pinfunction "PB2/BOOT1_48") (pintype "passive"))
    )
    (net (code "7") (name "/DOOR") (class "Default")
      (node (ref "R15") (pin "1") (pinfunction "1_1") (pintype "passive"))
      (node (ref "U2") (pin "57") (pinfunction "PG1/FSMC_A11_57") (pintype "passive"))
    )
    (net (code "8") (name "/DOOR_OUT") (class "Default")
      (node (ref "P5") (pin "3") (pinfunction "3_3") (pintype "passive"))
      (node (ref "继电器1") (pin "5") (pinfunction "FLA_5") (pintype "passive"))
    )
    (net (code "9") (name "/FB") (class "Default")
      (node (ref "C33") (pin "2") (pinfunction "2_2") (pintype "passive"))
      (node (ref "R26") (pin "1") (pintype "passive"))
      (node (ref "R29") (pin "2") (pintype "passive"))
      (node (ref "U5") (pin "1") (pinfunction "ADJ_1") (pintype "input"))
    )
    (net (code "10") (name "/FIFO_OE") (class "Default")
      (node (ref "P4") (pin "20") (pinfunction "20_20") (pintype "passive"))
      (node (ref "U2") (pin "132") (pinfunction "PG15_132") (pintype "passive"))
    )
    (net (code "11") (name "/FIFO_RCLK") (class "Default")
      (node (ref "P4") (pin "18") (pinfunction "18_18") (pintype "passive"))
      (node (ref "U2") (pin "127") (pinfunction "PG12/FSMC_NE4_127") (pintype "passive"))
    )
    (net (code "12") (name "/FIFO_RRST") (class "Default")
      (node (ref "P4") (pin "22") (pinfunction "22_22") (pintype "passive"))
      (node (ref "U2") (pin "129") (pinfunction "PG14/FSMC_A25_129") (pintype "passive"))
    )
    (net (code "13") (name "/FIFO_WEN") (class "Default")
      (node (ref "P4") (pin "19") (pinfunction "19_19") (pintype "passive"))
      (node (ref "U2") (pin "126") (pinfunction "PG11/FSMC_NCE4_2_126") (pintype "passive"))
    )
    (net (code "14") (name "/FIFO_WRST") (class "Default")
      (node (ref "P4") (pin "21") (pinfunction "21_21") (pintype "passive"))
      (node (ref "U2") (pin "122") (pinfunction "PD6/FSMC_NWAIT_122") (pintype "passive"))
    )
    (net (code "15") (name "/FSMC_D0") (class "Default")
      (node (ref "U2") (pin "85") (pinfunction "PD14/FSMC_D0_85") (pintype "passive"))
      (node (ref "U3") (pin "3") (pinfunction "D0_3") (pintype "passive"))
    )
    (net (code "16") (name "/FSMC_D1") (class "Default")
      (node (ref "U2") (pin "86") (pinfunction "PD15/FSMC_D1_86") (pintype "passive"))
      (node (ref "U3") (pin "4") (pinfunction "D1_4") (pintype "passive"))
    )
    (net (code "17") (name "/FSMC_D2") (class "Default")
      (node (ref "U2") (pin "114") (pinfunction "PD0/FSMC_D2_114") (pintype "passive"))
      (node (ref "U3") (pin "5") (pinfunction "D2_5") (pintype "passive"))
    )
    (net (code "18") (name "/FSMC_D3") (class "Default")
      (node (ref "U2") (pin "115") (pinfunction "PD1/FSMC_D3_115") (pintype "passive"))
      (node (ref "U3") (pin "6") (pinfunction "D3_6") (pintype "passive"))
    )
    (net (code "19") (name "/FSMC_D4") (class "Default")
      (node (ref "U2") (pin "58") (pinfunction "PE7/FSMC_D4_58") (pintype "passive"))
      (node (ref "U3") (pin "7") (pinfunction "D4_7") (pintype "passive"))
    )
    (net (code "20") (name "/FSMC_D5") (class "Default")
      (node (ref "U2") (pin "59") (pinfunction "PE8/FSMC_D5_59") (pintype "passive"))
      (node (ref "U3") (pin "8") (pinfunction "D5_8") (pintype "passive"))
    )
    (net (code "21") (name "/FSMC_D6") (class "Default")
      (node (ref "U2") (pin "60") (pinfunction "PE9/FSMC_D6_60") (pintype "passive"))
      (node (ref "U3") (pin "9") (pinfunction "D6_9") (pintype "passive"))
    )
    (net (code "22") (name "/FSMC_D7") (class "Default")
      (node (ref "U2") (pin "63") (pinfunction "PE10/FSMC_D7_63") (pintype "passive"))
      (node (ref "U3") (pin "10") (pinfunction "D7_10") (pintype "passive"))
    )
    (net (code "23") (name "/FSMC_D8") (class "Default")
      (node (ref "U2") (pin "64") (pinfunction "PE11/FSMC_D8_64") (pintype "passive"))
      (node (ref "U3") (pin "11") (pinfunction "D8_11") (pintype "passive"))
    )
    (net (code "24") (name "/FSMC_D9") (class "Default")
      (node (ref "U2") (pin "65") (pinfunction "PE12/FSMC_D9_65") (pintype "passive"))
      (node (ref "U3") (pin "12") (pinfunction "D9_12") (pintype "passive"))
    )
    (net (code "25") (name "/FSMC_D10") (class "Default")
      (node (ref "U2") (pin "66") (pinfunction "PE13/FSMC_D10_66") (pintype "passive"))
      (node (ref "U3") (pin "13") (pinfunction "D10_13") (pintype "passive"))
    )
    (net (code "26") (name "/FSMC_D11") (class "Default")
      (node (ref "U2") (pin "67") (pinfunction "PE14/FSMC_D11_67") (pintype "passive"))
      (node (ref "U3") (pin "14") (pinfunction "D11_14") (pintype "passive"))
    )
    (net (code "27") (name "/FSMC_D12") (class "Default")
      (node (ref "U2") (pin "68") (pinfunction "PE15/FSMC_D12_68") (pintype "passive"))
      (node (ref "U3") (pin "15") (pinfunction "D12_15") (pintype "passive"))
    )
    (net (code "28") (name "/FSMC_D13") (class "Default")
      (node (ref "U2") (pin "77") (pinfunction "PD8/FSMC_D13_77") (pintype "passive"))
      (node (ref "U3") (pin "16") (pinfunction "D13_16") (pintype "passive"))
    )
    (net (code "29") (name "/FSMC_D14") (class "Default")
      (node (ref "U2") (pin "78") (pinfunction "PD9/FSMC_D14_78") (pintype "passive"))
      (node (ref "U3") (pin "17") (pinfunction "D14_17") (pintype "passive"))
    )
    (net (code "30") (name "/FSMC_D15") (class "Default")
      (node (ref "U2") (pin "79") (pinfunction "PD10/FSMC_D15_79") (pintype "passive"))
      (node (ref "U3") (pin "18") (pinfunction "D15_18") (pintype "passive"))
    )
    (net (code "31") (name "/GREEN") (class "Default")
      (node (ref "GREEN1") (pin "1") (pinfunction "A_1") (pintype "passive"))
      (node (ref "U2") (pin "88") (pinfunction "PG3/FSMC_A13_88") (pintype "passive"))
    )
    (net (code "32") (name "/GSM_EN") (class "Default")
      (node (ref "U1") (pin "24") (pinfunction "IO29_24") (pintype "passive"))
      (node (ref "U2") (pin "50") (pinfunction "PF12/FSMC_A6_50") (pintype "passive"))
    )
    (net (code "33") (name "/GSM_RF") (class "Default")
      (node (ref "IPX1") (pin "2") (pinfunction "DATA_2") (pintype "passive"))
      (node (ref "U1") (pin "45") (pinfunction "GSM_RF_45") (pintype "passive"))
    )
    (net (code "34") (name "/GSM_RST") (class "Default")
      (node (ref "R2") (pin "1") (pinfunction "1_1") (pintype "passive"))
      (node (ref "U2") (pin "53") (pinfunction "PF13/FSMC_A7_53") (pintype "passive"))
    )
    (net (code "35") (name "/IIC_OUT") (class "Default")
      (node (ref "R32") (pin "2") (pinfunction "2_2") (pintype "passive"))
      (node (ref "U2") (pin "5") (pinfunction "PE6/TRACED3/FSMC_A22_5") (pintype "passive"))
      (node (ref "U8") (pin "7") (pinfunction "SQW/OUT_7") (pintype "output"))
    )
    (net (code "36") (name "/IIC_SCL") (class "Default")
      (node (ref "R27") (pin "1") (pinfunction "1_1") (pintype "passive"))
      (node (ref "U2") (pin "139") (pinfunction "PB8/TIM4_CH3/SDIO_D4_139") (pintype "passive"))
      (node (ref "U8") (pin "6") (pinfunction "SCL_6") (pintype "input"))
    )
    (net (code "37") (name "/IIC_SDA") (class "Default")
      (node (ref "R28") (pin "1") (pinfunction "1_1") (pintype "passive"))
      (node (ref "U2") (pin "140") (pinfunction "PB9/TIM4_CH4/SDIO_D5_140") (pintype "passive"))
      (node (ref "U8") (pin "5") (pinfunction "SDA_5") (pintype "bidirectional"))
    )
    (net (code "38") (name "/KEY_IN") (class "Default")
      (node (ref "P6") (pin "3") (pinfunction "3_3") (pintype "passive"))
      (node (ref "U2") (pin "22") (pinfunction "PF10/ADC3_IN8/FSMC_INTR_22") (pintype "passive"))
    )
    (net (code "39") (name "/KEY_OUT") (class "Default")
      (node (ref "P7") (pin "3") (pinfunction "3_3") (pintype "passive"))
      (node (ref "U2") (pin "49") (pinfunction "PF11/FSMC_NIOS16_49") (pintype "passive"))
    )
    (net (code "40") (name "/LCD_CS") (class "Default")
      (node (ref "U2") (pin "124") (pinfunction "PG9/FSMC_NE2/FSMC_NCE3_124") (pintype "passive"))
      (node (ref "U3") (pin "19") (pinfunction "CS_19") (pintype "passive"))
    )
    (net (code "41") (name "/LCD_RD") (class "Default")
      (node (ref "U2") (pin "118") (pinfunction "PD4/FSMC_NOE_118") (pintype "passive"))
      (node (ref "U3") (pin "22") (pinfunction "RD_22") (pintype "passive"))
    )
    (net (code "42") (name "/LCD_RS") (class "Default")
      (node (ref "U2") (pin "10") (pinfunction "PF0/FSMC_A0_10") (pintype "passive"))
      (node (ref "U3") (pin "20") (pinfunction "RS_20") (pintype "passive"))
    )
    (net (code "43") (name "/LCD_RST") (class "Default")
      (node (ref "C12") (pin "2") (pinfunction "2_2") (pintype "passive"))
      (node (ref "R14") (pin "1") (pinfunction "1_1") (pintype "passive"))
      (node (ref "S2") (pin "2") (pinfunction "2_2") (pintype "passive"))
      (node (ref "U2") (pin "25") (pinfunction "NRST_25") (pintype "passive"))
      (node (ref "U3") (pin "23") (pinfunction "RST_23") (pintype "passive"))
    )
    (net (code "44") (name "/LCD_WR") (class "Default")
      (node (ref "U2") (pin "119") (pinfunction "PD5/FSMC_NWE_119") (pintype "passive"))
      (node (ref "U3") (pin "21") (pinfunction "WR_21") (pintype "passive"))
    )
    (net (code "45") (name "/NET_STATE") (class "Default")
      (node (ref "NET1") (pin "1") (pinfunction "A_1") (pintype "passive"))
      (node (ref "U1") (pin "26") (pinfunction "IO27_26") (pintype "passive"))
    )
    (net (code "46") (name "/OV_D0") (class "Default")
      (node (ref "P4") (pin "14") (pinfunction "14_14") (pintype "passive"))
      (node (ref "U2") (pin "26") (pinfunction "PC0/ADC123_IN10_26") (pintype "passive"))
    )
    (net (code "47") (name "/OV_D1") (class "Default")
      (node (ref "P4") (pin "13") (pinfunction "13_13") (pintype "passive"))
      (node (ref "U2") (pin "27") (pinfunction "PC1/ADC123_IN11_27") (pintype "passive"))
    )
    (net (code "48") (name "/OV_D2") (class "Default")
      (node (ref "P4") (pin "12") (pinfunction "12_12") (pintype "passive"))
      (node (ref "U2") (pin "28") (pinfunction "PC2/ADC123_IN12_28") (pintype "passive"))
    )
    (net (code "49") (name "/OV_D3") (class "Default")
      (node (ref "P4") (pin "11") (pinfunction "11_11") (pintype "passive"))
      (node (ref "U2") (pin "29") (pinfunction "PC3/ADC123_IN13_29") (pintype "passive"))
    )
    (net (code "50") (name "/OV_D4") (class "Default")
      (node (ref "P4") (pin "10") (pinfunction "10_10") (pintype "passive"))
      (node (ref "U2") (pin "44") (pinfunction "PC4/ADC12_IN14_44") (pintype "passive"))
    )
    (net (code "51") (name "/OV_D5") (class "Default")
      (node (ref "P4") (pin "9") (pinfunction "9_9") (pintype "passive"))
      (node (ref "U2") (pin "45") (pinfunction "PC5/ADC12_IN15_45") (pintype "passive"))
    )
    (net (code "52") (name "/OV_D6") (class "Default")
      (node (ref "P4") (pin "8") (pinfunction "8_8") (pintype "passive"))
      (node (ref "U2") (pin "96") (pinfunction "PC6/I2S2_MCK/TIM8_CH1/SDIO_D6_96") (pintype "passive"))
    )
    (net (code "53") (name "/OV_D7") (class "Default")
      (node (ref "P4") (pin "7") (pinfunction "7_7") (pintype "passive"))
      (node (ref "U2") (pin "97") (pinfunction "PC7/I2S3_MCK/TIM8_CH2/SDIO_D7_97") (pintype "passive"))
    )
    (net (code "54") (name "/OV_SCL") (class "Default")
      (node (ref "P4") (pin "3") (pinfunction "3_3") (pintype "passive"))
      (node (ref "U2") (pin "117") (pinfunction "PD3/FSMC_CLK_117") (pintype "passive"))
    )
    (net (code "55") (name "/OV_SDA") (class "Default")
      (node (ref "P4") (pin "4") (pinfunction "4_4") (pintype "passive"))
      (node (ref "U2") (pin "128") (pinfunction "PG13/FSMC_A24_128") (pintype "passive"))
    )
    (net (code "56") (name "/OV_STR") (class "Default")
      (node (ref "P4") (pin "17") (pinfunction "17_17") (pintype "passive"))
    )
    (net (code "57") (name "/OV_VSYNC") (class "Default")
      (node (ref "P4") (pin "5") (pinfunction "5_5") (pintype "passive"))
      (node (ref "U2") (pin "100") (pinfunction "PA8/USART1_CK/TIM1_CH1/MCO_100") (pintype "passive"))
    )
    (net (code "58") (name "/PA2") (class "Default")
      (node (ref "U1") (pin "53") (pinfunction "UART1_RXD/IO0_53") (pintype "passive"))
      (node (ref "U2") (pin "36") (pinfunction "PA2/USART2_TX/ADC123_IN2/TIM5_CH3/TIM2_CH3_36") (pintype "passive"))
    )
    (net (code "59") (name "/PA3") (class "Default")
      (node (ref "U1") (pin "54") (pinfunction "UART1_TXD/IO1_54") (pintype "passive"))
      (node (ref "U2") (pin "37") (pinfunction "PA3/USART2_RX/ADC123_IN3/TIM5_CH4/TIM2_CH4_37") (pintype "passive"))
    )
    (net (code "60") (name "/PA9") (class "Default")
      (node (ref "P1") (pin "4") (pinfunction "4_4") (pintype "passive"))
      (node (ref "U2") (pin "101") (pinfunction "PA9/USART1_TX/TIM1_CH2_101") (pintype "passive"))
    )
    (net (code "61") (name "/PA10") (class "Default")
      (node (ref "P1") (pin "3") (pinfunction "3_3") (pintype "passive"))
      (node (ref "U2") (pin "102") (pinfunction "PA10/USART1_RX/TIM1_CH3_102") (pintype "passive"))
    )
    (net (code "62") (name "/PA13") (class "Default")
      (node (ref "P2") (pin "4") (pinfunction "4_4") (pintype "passive"))
      (node (ref "U2") (pin "105") (pinfunction "PA13/JTMS_SWDIO_105") (pintype "passive"))
    )
    (net (code "63") (name "/PA14") (class "Default")
      (node (ref "P2") (pin "5") (pinfunction "5_5") (pintype "passive"))
      (node (ref "U2") (pin "109") (pinfunction "PA14/JTCK_SWCLK_109") (pintype "passive"))
    )
    (net (code "64") (name "/PB0") (class "Default")
      (node (ref "R10") (pin "1") (pinfunction "1_1") (pintype "passive"))
      (node (ref "U2") (pin "46") (pinfunction "PB0/ADC12_IN8/TIM3_CH3/TIM8_CH2N_46") (pintype "passive"))
      (node (ref "U2") (pin "55") (pinfunction "PF15/FSMC_A9_55") (pintype "passive"))
      (node (ref "U4") (pin "1") (pinfunction "RST_1") (pintype "passive"))
    )
    (net (code "65") (name "/PB1") (class "Default")
      (node (ref "U2") (pin "47") (pinfunction "PB1/ADC12_IN9/TIM3_CH4/TIM8_CH3N_47") (pintype "passive"))
      (node (ref "U2") (pin "54") (pinfunction "PF14/FSMC_A8_54") (pintype "passive"))
      (node (ref "U4") (pin "3") (pinfunction "EN_3") (pintype "passive"))
    )
    (net (code "66") (name "/PB3") (class "Default")
      (node (ref "U2") (pin "133") (pinfunction "PB3/JTDO/TRACESWO/SPI3_SCK/I2S3_CK_133") (pintype "passive"))
      (node (ref "U3") (pin "29") (pinfunction "TP_SCK_29") (pintype "passive"))
    )
    (net (code "67") (name "/PB4") (class "Default")
      (node (ref "U2") (pin "134") (pinfunction "PB4/JNTRST/SPI3_MISO_134") (pintype "passive"))
      (node (ref "U3") (pin "25") (pinfunction "TP_SO_25") (pintype "passive"))
    )
    (net (code "68") (name "/PB5") (class "Default")
      (node (ref "U2") (pin "135") (pinfunction "PB5/I2C1_SMBAI/SPI3_MOSI/I2S3_SD_135") (pintype "passive"))
      (node (ref "U3") (pin "27") (pinfunction "TP_SI_27") (pintype "passive"))
    )
    (net (code "69") (name "/PB6") (class "Default")
      (node (ref "U2") (pin "136") (pinfunction "PB6/I2C1_SCL/TIM4_CH1_136") (pintype "passive"))
      (node (ref "U3") (pin "26") (pinfunction "TP_IRQ_26") (pintype "passive"))
    )
    (net (code "70") (name "/PB10") (class "Default")
      (node (ref "U2") (pin "69") (pinfunction "PB10/I2C2_SCL/USART3_TX_69") (pintype "passive"))
      (node (ref "U4") (pin "15") (pinfunction "RXD0_15") (pintype "passive"))
    )
    (net (code "71") (name "/PB11") (class "Default")
      (node (ref "U2") (pin "70") (pinfunction "PB11/I2C2_SDA/USART3_RX_70") (pintype "passive"))
      (node (ref "U4") (pin "16") (pinfunction "TXD0_16") (pintype "passive"))
    )
    (net (code "72") (name "/PB13") (class "Default")
      (node (ref "P9") (pin "7") (pinfunction "7_7") (pintype "passive"))
      (node (ref "U2") (pin "74") (pinfunction "PB13/SPI2_SCK/I2S2_CK/USART3_CTS/TIM1_CH1N_74") (pintype "passive"))
    )
    (net (code "73") (name "/PB14") (class "Default")
      (node (ref "P9") (pin "5") (pinfunction "5_5") (pintype "passive"))
      (node (ref "U2") (pin "75") (pinfunction "PB14/SPI2_MISO/USART3_RTS/TIM1_CH2N_75") (pintype "passive"))
    )
    (net (code "74") (name "/PB15") (class "Default")
      (node (ref "P9") (pin "6") (pinfunction "6_6") (pintype "passive"))
      (node (ref "U2") (pin "76") (pinfunction "PB15/SPI2_MOSI/I2S2_SD/TIM1_CH3N_76") (pintype "passive"))
    )
    (net (code "75") (name "/PC8") (class "Default")
      (node (ref "R22") (pin "2") (pinfunction "2_2") (pintype "passive"))
      (node (ref "TF1") (pin "7") (pinfunction "D0_7") (pintype "passive"))
      (node (ref "U2") (pin "98") (pinfunction "PC8/TIM8_CH3/SDIO_D0_98") (pintype "passive"))
    )
    (net (code "76") (name "/PC9") (class "Default")
      (node (ref "R23") (pin "2") (pinfunction "2_2") (pintype "passive"))
      (node (ref "TF1") (pin "8") (pinfunction "D1_8") (pintype "passive"))
      (node (ref "U2") (pin "99") (pinfunction "PC9/TIM8_CH4/SDIO_D1_99") (pintype "passive"))
    )
    (net (code "77") (name "/PC10") (class "Default")
      (node (ref "R17") (pin "2") (pinfunction "2_2") (pintype "passive"))
      (node (ref "TF1") (pin "1") (pinfunction "D2_1") (pintype "passive"))
      (node (ref "U2") (pin "111") (pinfunction "PC10/UART4_TX/SDIO_D2_111") (pintype "passive"))
    )
    (net (code "78") (name "/PC11") (class "Default")
      (node (ref "R18") (pin "2") (pinfunction "2_2") (pintype "passive"))
      (node (ref "TF1") (pin "2") (pinfunction "D3_2") (pintype "passive"))
      (node (ref "U2") (pin "112") (pinfunction "PC11/UART4_RX/SDIO_D3_112") (pintype "passive"))
    )
    (net (code "79") (name "/PC12") (class "Default")
      (node (ref "R20") (pin "2") (pinfunction "2_2") (pintype "passive"))
      (node (ref "TF1") (pin "5") (pinfunction "CLK_5") (pintype "passive"))
      (node (ref "U2") (pin "113") (pinfunction "PC12/UART5_TX/SDIO_CK_113") (pintype "passive"))
    )
    (net (code "80") (name "/PD2") (class "Default")
      (node (ref "R19") (pin "2") (pinfunction "2_2") (pintype "passive"))
      (node (ref "TF1") (pin "3") (pinfunction "CMD_3") (pintype "passive"))
      (node (ref "U2") (pin "116") (pinfunction "PD2/TIM3_ETR/UART5_RX/SDIO_CMD_116") (pintype "passive"))
    )
    (net (code "81") (name "/PE2") (class "Default")
      (node (ref "U2") (pin "1") (pinfunction "PE2/TRACECK/FSMC_A23_1") (pintype "passive"))
      (node (ref "U3") (pin "31") (pinfunction "TP-CS_31") (pintype "passive"))
    )
    (net (code "82") (name "/PG2") (class "Default")
      (node (ref "RED1") (pin "1") (pinfunction "A_1") (pintype "passive"))
      (node (ref "U2") (pin "87") (pinfunction "PG2/FSMC_A12_87") (pintype "passive"))
    )
    (net (code "83") (name "/PG4") (class "Default")
      (node (ref "STATE1") (pin "1") (pinfunction "A_1") (pintype "passive"))
      (node (ref "U2") (pin "89") (pinfunction "PG4/FSMC_A14_89") (pintype "passive"))
    )
    (net (code "84") (name "/PG6") (class "Default")
      (node (ref "P9") (pin "2") (pinfunction "2_2") (pintype "passive"))
      (node (ref "U2") (pin "91") (pinfunction "PG6/FSMC_INT2_91") (pintype "passive"))
    )
    (net (code "85") (name "/PG7") (class "Default")
      (node (ref "P9") (pin "4") (pinfunction "4_4") (pintype "passive"))
      (node (ref "U2") (pin "92") (pinfunction "PG7/FSMC_INT3_92") (pintype "passive"))
    )
    (net (code "86") (name "/PG8") (class "Default")
      (node (ref "P9") (pin "8") (pinfunction "8_8") (pintype "passive"))
      (node (ref "U2") (pin "93") (pinfunction "PG8_93") (pintype "passive"))
    )
    (net (code "87") (name "/PWR_KEY") (class "Default")
      (node (ref "R1") (pin "1") (pinfunction "1_1") (pintype "passive"))
      (node (ref "U1") (pin "9") (pinfunction "PWR_KEY_9") (pintype "passive"))
    )
    (net (code "88") (name "/SIM_CLK") (class "Default")
      (node (ref "P3") (pin "5") (pinfunction "CLK_5") (pintype "passive"))
      (node (ref "U1") (pin "41") (pinfunction "SIM_CLK_41") (pintype "passive"))
    )
    (net (code "89") (name "/SIM_DIO") (class "Default")
      (node (ref "P3") (pin "6") (pinfunction "IO_6") (pintype "passive"))
      (node (ref "U1") (pin "39") (pinfunction "SIM_DIO_39") (pintype "passive"))
    )
    (net (code "90") (name "/SIM_RST") (class "Default")
      (node (ref "P3") (pin "3") (pinfunction "RST_3") (pintype "passive"))
      (node (ref "U1") (pin "42") (pinfunction "SIM_RST_42") (pintype "passive"))
    )
    (net (code "91") (name "CAME_3.3") (class "Default")
      (node (ref "C2") (pin "1") (pinfunction "1_1") (pintype "passive"))
      (node (ref "C40") (pin "1") (pinfunction "1_1") (pintype "passive"))
      (node (ref "P4") (pin "1") (pinfunction "1_1") (pintype "passive"))
      (node (ref "U10") (pin "2") (pinfunction "Vout_2") (pintype "passive"))
    )
    (net (code "92") (name "DGND") (class "Default")
      (node (ref "C12") (pin "1") (pinfunction "1_1") (pintype "passive"))
      (node (ref "C13") (pin "1") (pinfunction "1_1") (pintype "passive"))
      (node (ref "C14") (pin "1") (pinfunction "1_1") (pintype "passive"))
      (node (ref "C15") (pin "1") (pinfunction "1_1") (pintype "passive"))
      (node (ref "C16") (pin "1") (pinfunction "1_1") (pintype "passive"))
      (node (ref "C17") (pin "1") (pinfunction "1_1") (pintype "passive"))
      (node (ref "C18") (pin "1") (pinfunction "1_1") (pintype "passive"))
      (node (ref "C19") (pin "1") (pinfunction "1_1") (pintype "passive"))
      (node (ref "C20") (pin "1") (pinfunction "1_1") (pintype "passive"))
      (node (ref "C21") (pin "1") (pinfunction "1_1") (pintype "passive"))
      (node (ref "C22") (pin "1") (pinfunction "1_1") (pintype "passive"))
      (node (ref "C5") (pin "1") (pinfunction "1_1") (pintype "passive"))
      (node (ref "C6") (pin "1") (pinfunction "1_1") (pintype "passive"))
      (node (ref "P1") (pin "5") (pinfunction "5_5") (pintype "passive"))
      (node (ref "P2") (pin "3") (pinfunction "3_3") (pintype "passive"))
      (node (ref "P6") (pin "2") (pinfunction "2_2") (pintype "passive"))
      (node (ref "P7") (pin "2") (pinfunction "2_2") (pintype "passive"))
      (node (ref "R11") (pin "2") (pinfunction "2_2") (pintype "passive"))
      (node (ref "R12") (pin "2") (pinfunction "2_2") (pintype "passive"))
      (node (ref "R24") (pin "1") (pinfunction "1_1") (pintype "passive"))
      (node (ref "S2") (pin "1") (pinfunction "1_1") (pintype "passive"))
      (node (ref "U2") (pin "107") (pinfunction "VSS_107") (pintype "passive"))
      (node (ref "U2") (pin "120") (pinfunction "VSS_120") (pintype "passive"))
      (node (ref "U2") (pin "130") (pinfunction "VSS_130") (pintype "passive"))
      (node (ref "U2") (pin "143") (pinfunction "VSS_143") (pintype "passive"))
      (node (ref "U2") (pin "16") (pinfunction "VSS_16") (pintype "passive"))
      (node (ref "U2") (pin "38") (pinfunction "VSS_38") (pintype "passive"))
      (node (ref "U2") (pin "51") (pinfunction "VSS_51") (pintype "passive"))
      (node (ref "U2") (pin "61") (pinfunction "VSS_61") (pintype "passive"))
      (node (ref "U2") (pin "71") (pinfunction "VSS_71") (pintype "passive"))
      (node (ref "U2") (pin "83") (pinfunction "VSS_83") (pintype "passive"))
      (node (ref "U2") (pin "94") (pinfunction "VSS_94") (pintype "passive"))
    )
    (net (code "93") (name "GND") (class "Default")
      (node (ref "BAT") (pin "2") (pinfunction "GND_2") (pintype "passive"))
      (node (ref "C1") (pin "2") (pinfunction "2_2") (pintype "passive"))
      (node (ref "C10") (pin "1") (pinfunction "1_1") (pintype "passive"))
      (node (ref "C11") (pin "1") (pinfunction "1_1") (pintype "passive"))
      (node (ref "C2") (pin "2") (pinfunction "2_2") (pintype "passive"))
      (node (ref "C23") (pin "1") (pinfunction "1_1") (pintype "passive"))
      (node (ref "C24") (pin "1") (pinfunction "2_1") (pintype "passive"))
      (node (ref "C25") (pin "2") (pinfunction "2_2") (pintype "passive"))
      (node (ref "C26") (pin "1") (pinfunction "2_1") (pintype "passive"))
      (node (ref "C27") (pin "1") (pinfunction "2_1") (pintype "passive"))
      (node (ref "C28") (pin "1") (pinfunction "2_1") (pintype "passive"))
      (node (ref "C29") (pin "2") (pinfunction "2_2") (pintype "passive"))
      (node (ref "C3") (pin "1") (pinfunction "1_1") (pintype "passive"))
      (node (ref "C30") (pin "2") (pinfunction "2_2") (pintype "passive"))
      (node (ref "C31") (pin "2") (pinfunction "2_2") (pintype "passive"))
      (node (ref "C32") (pin "2") (pinfunction "2_2") (pintype "passive"))
      (node (ref "C33") (pin "1") (pinfunction "1_1") (pintype "passive"))
      (node (ref "C34") (pin "1") (pinfunction "1_1") (pintype "passive"))
      (node (ref "C35") (pin "2") (pinfunction "2_2") (pintype "passive"))
      (node (ref "C36") (pin "2") (pinfunction "2_2") (pintype "passive"))
      (node (ref "C37") (pin "2") (pinfunction "2_2") (pintype "passive"))
      (node (ref "C38") (pin "1") (pinfunction "1_1") (pintype "passive"))
      (node (ref "C39") (pin "2") (pinfunction "2_2") (pintype "passive"))
      (node (ref "C4") (pin "1") (pinfunction "1_1") (pintype "passive"))
      (node (ref "C40") (pin "2") (pinfunction "2_2") (pintype "passive"))
      (node (ref "C41") (pin "2") (pinfunction "2_2") (pintype "passive"))
      (node (ref "C42") (pin "2") (pinfunction "2_2") (pintype "passive"))
      (node (ref "C7") (pin "1") (pinfunction "1_1") (pintype "passive"))
      (node (ref "C8") (pin "1") (pinfunction "1_1") (pintype "passive"))
      (node (ref "C9") (pin "1") (pinfunction "1_1") (pintype "passive"))
      (node (ref "D4") (pin "1") (pinfunction "A_1") (pintype "passive"))
      (node (ref "IPX1") (pin "1") (pinfunction "GND_1") (pintype "passive"))
      (node (ref "IPX1") (pin "3") (pinfunction "GND_3") (pintype "passive"))
      (node (ref "P3") (pin "2") (pinfunction "GND_2") (pintype "passive"))
      (node (ref "P3") (pin "7") (pinfunction "GND_7") (pintype "passive"))
      (node (ref "P3") (pin "8") (pinfunction "GND_8") (pintype "passive"))
      (node (ref "P4") (pin "2") (pinfunction "2_2") (pintype "passive"))
      (node (ref "P5") (pin "2") (pinfunction "2_2") (pintype "passive"))
      (node (ref "P8") (pin "3") (pinfunction "3_3") (pintype "power_in"))
      (node (ref "P9") (pin "3") (pinfunction "3_3") (pintype "passive"))
      (node (ref "Q1") (pin "2") (pinfunction "E_2") (pintype "passive"))
      (node (ref "Q2") (pin "2") (pinfunction "E_2") (pintype "passive"))
      (node (ref "Q3") (pin "2") (pinfunction "E_2") (pintype "passive"))
      (node (ref "R1") (pin "2") (pinfunction "2_2") (pintype "passive"))
      (node (ref "R16") (pin "2") (pinfunction "2_2") (pintype "passive"))
      (node (ref "R24") (pin "2") (pinfunction "2_2") (pintype "passive"))
      (node (ref "R25") (pin "2") (pinfunction "2_2") (pintype "passive"))
      (node (ref "R29") (pin "1") (pintype "passive"))
      (node (ref "R3") (pin "2") (pinfunction "2_2") (pintype "passive"))
      (node (ref "R31") (pin "1") (pinfunction "1_1") (pintype "passive"))
      (node (ref "R4") (pin "2") (pinfunction "2_2") (pintype "passive"))
      (node (ref "R5") (pin "2") (pinfunction "2_2") (pintype "passive"))
      (node (ref "R6") (pin "2") (pinfunction "2_2") (pintype "passive"))
      (node (ref "R7") (pin "2") (pinfunction "2_2") (pintype "passive"))
      (node (ref "R9") (pin "2") (pinfunction "2_2") (pintype "passive"))
      (node (ref "S1") (pin "2") (pinfunction "2_2") (pintype "passive"))
      (node (ref "TF1") (pin "6") (pinfunction "GND_6") (pintype "passive"))
      (node (ref "U1") (pin "10") (pinfunction "GND_10") (pintype "passive"))
      (node (ref "U1") (pin "27") (pinfunction "GND_27") (pintype "passive"))
      (node (ref "U1") (pin "29") (pinfunction "GND_29") (pintype "passive"))
      (node (ref "U1") (pin "44") (pinfunction "GND_44") (pintype "passive"))
      (node (ref "U1") (pin "46") (pinfunction "GND_46") (pintype "passive"))
      (node (ref "U1") (pin "55") (pinfunction "GND_PAD_55") (pintype "passive"))
      (node (ref "U1") (pin "56") (pinfunction "GND_PAD_56") (pintype "passive"))
      (node (ref "U10") (pin "1") (pinfunction "GND_1") (pintype "passive"))
      (node (ref "U11") (pin "1") (pinfunction "GND_1") (pintype "passive"))
      (node (ref "U2") (pin "30") (pinfunction "VSSA_30") (pintype "passive"))
      (node (ref "U2") (pin "31") (pinfunction "Vref-_31") (pintype "passive"))
      (node (ref "U3") (pin "2") (pinfunction "GND_2") (pintype "passive"))
      (node (ref "U4") (pin "9") (pinfunction "GND_9") (pintype "passive"))
      (node (ref "U5") (pin "2") (pinfunction "~{ON}/OFF_2") (pintype "input"))
      (node (ref "U5") (pin "4") (pinfunction "GND_4") (pintype "power_in"))
      (node (ref "U6") (pin "1") (pinfunction "GND_1") (pintype "passive"))
      (node (ref "U7") (pin "1") (pinfunction "GND_1") (pintype "passive"))
      (node (ref "U8") (pin "4") (pinfunction "GND_4") (pintype "power_in"))
      (node (ref "U9") (pin "2") (pinfunction "GND_2") (pintype "passive"))
      (node (ref "USB1") (pin "5") (pinfunction "GND_5") (pintype "passive"))
      (node (ref "继电器1") (pin "1") (pinfunction "FLB_1") (pintype "passive"))
    )
    (net (code "94") (name "GSM_VCC") (class "Default")
      (node (ref "C34") (pin "2") (pinfunction "2_2") (pintype "passive"))
      (node (ref "C36") (pin "1") (pinfunction "1_1") (pintype "passive"))
      (node (ref "C37") (pin "1") (pinfunction "1_1") (pintype "passive"))
      (node (ref "C38") (pin "2") (pinfunction "2_2") (pintype "passive"))
      (node (ref "L2") (pin "1") (pinfunction "1_1") (pintype "passive"))
      (node (ref "P3") (pin "1") (pinfunction "VCC_1") (pintype "passive"))
      (node (ref "R30") (pin "2") (pinfunction "2_2") (pintype "passive"))
      (node (ref "U1") (pin "11") (pinfunction "VBAT_11") (pintype "passive"))
      (node (ref "U1") (pin "12") (pinfunction "VBAT_12") (pintype "passive"))
      (node (ref "U1") (pin "40") (pinfunction "VSIM_40") (pintype "passive"))
      (node (ref "U1") (pin "43") (pinfunction "VIO_43") (pintype "passive"))
    )
    (net (code "95") (name "LCD_3.3") (class "Default")
      (node (ref "C1") (pin "1") (pinfunction "1_1") (pintype "passive"))
      (node (ref "C30") (pin "1") (pinfunction "1_1") (pintype "passive"))
      (node (ref "U3") (pin "1") (pinfunction "VCC_1") (pintype "passive"))
      (node (ref "U6") (pin "2") (pinfunction "Vout_2") (pintype "passive"))
    )
    (net (code "96") (name "Net-(BEEP1-G)") (class "Default")
      (node (ref "BEEP1") (pin "2") (pinfunction "G_2") (pintype "passive"))
      (node (ref "D3") (pin "1") (pinfunction "A_1") (pintype "passive"))
      (node (ref "Q3") (pin "3") (pinfunction "C_3") (pintype "passive"))
    )
    (net (code "97") (name "Net-(D2-A)") (class "Default")
      (node (ref "D2") (pin "1") (pinfunction "A_1") (pintype "passive"))
      (node (ref "Q2") (pin "3") (pinfunction "C_3") (pintype "passive"))
      (node (ref "继电器1") (pin "3") (pinfunction "FLA_3") (pintype "passive"))
    )
    (net (code "98") (name "Net-(D4-K)") (class "Default")
      (node (ref "D4") (pin "2") (pinfunction "K_2") (pintype "passive"))
      (node (ref "L1") (pin "2") (pinfunction "2_2") (pintype "passive"))
      (node (ref "U5") (pin "5") (pinfunction "OUT_5") (pintype "power_in"))
    )
    (net (code "99") (name "Net-(FB1-Pad1)") (class "Default")
      (node (ref "FB1") (pin "1") (pinfunction "1_1") (pintype "passive"))
      (node (ref "P8") (pin "1") (pinfunction "1_1") (pintype "power_in"))
    )
    (net (code "100") (name "Net-(GREEN1-K)") (class "Default")
      (node (ref "GREEN1") (pin "2") (pinfunction "K_2") (pintype "passive"))
      (node (ref "R7") (pin "1") (pinfunction "1_1") (pintype "passive"))
    )
    (net (code "101") (name "Net-(NET1-K)") (class "Default")
      (node (ref "NET1") (pin "2") (pinfunction "K_2") (pintype "passive"))
      (node (ref "R4") (pin "1") (pinfunction "1_1") (pintype "passive"))
    )
    (net (code "102") (name "Net-(POWER1-K)") (class "Default")
      (node (ref "POWER1") (pin "2") (pinfunction "K_2") (pintype "passive"))
      (node (ref "R5") (pin "1") (pinfunction "1_1") (pintype "passive"))
    )
    (net (code "103") (name "Net-(Q1-B)") (class "Default")
      (node (ref "Q1") (pin "1") (pinfunction "B_1") (pintype "passive"))
      (node (ref "R2") (pin "2") (pinfunction "2_2") (pintype "passive"))
      (node (ref "R3") (pin "1") (pinfunction "1_1") (pintype "passive"))
    )
    (net (code "104") (name "Net-(Q1-C)") (class "Default")
      (node (ref "Q1") (pin "3") (pinfunction "C_3") (pintype "passive"))
      (node (ref "U1") (pin "18") (pinfunction "RESET_18") (pintype "passive"))
    )
    (net (code "105") (name "Net-(Q2-B)") (class "Default")
      (node (ref "Q2") (pin "1") (pinfunction "B_1") (pintype "passive"))
      (node (ref "R15") (pin "2") (pinfunction "2_2") (pintype "passive"))
      (node (ref "R16") (pin "1") (pinfunction "1_1") (pintype "passive"))
    )
    (net (code "106") (name "Net-(Q3-B)") (class "Default")
      (node (ref "Q3") (pin "1") (pinfunction "B_1") (pintype "passive"))
      (node (ref "R21") (pin "2") (pinfunction "2_2") (pintype "passive"))
      (node (ref "R25") (pin "1") (pinfunction "1_1") (pintype "passive"))
    )
    (net (code "107") (name "Net-(R10-Pad2)") (class "Default")
      (node (ref "R10") (pin "2") (pinfunction "2_2") (pintype "passive"))
      (node (ref "S1") (pin "1") (pinfunction "1_1") (pintype "passive"))
    )
    (net (code "108") (name "Net-(RED1-K)") (class "Default")
      (node (ref "R6") (pin "1") (pinfunction "1_1") (pintype "passive"))
      (node (ref "RED1") (pin "2") (pinfunction "K_2") (pintype "passive"))
    )
    (net (code "109") (name "Net-(STATE1-K)") (class "Default")
      (node (ref "R9") (pin "1") (pinfunction "1_1") (pintype "passive"))
      (node (ref "STATE1") (pin "2") (pinfunction "K_2") (pintype "passive"))
    )
    (net (code "110") (name "Net-(U2-OSC_IN)") (class "Default")
      (node (ref "C5") (pin "2") (pinfunction "2_2") (pintype "passive"))
      (node (ref "R8") (pin "2") (pinfunction "2_2") (pintype "passive"))
      (node (ref "U2") (pin "23") (pinfunction "OSC_IN_23") (pintype "passive"))
      (node (ref "Y2") (pin "2") (pinfunction "OSC2_2") (pintype "passive"))
    )
    (net (code "111") (name "Net-(U2-OSC_OUT)") (class "Default")
      (node (ref "C6") (pin "2") (pinfunction "2_2") (pintype "passive"))
      (node (ref "R8") (pin "1") (pinfunction "1_1") (pintype "passive"))
      (node (ref "U2") (pin "24") (pinfunction "OSC_OUT_24") (pintype "passive"))
      (node (ref "Y2") (pin "1") (pinfunction "OSC1_1") (pintype "passive"))
    )
    (net (code "112") (name "Net-(U2-PC14-OSC32_IN)") (class "Default")
      (node (ref "C3") (pin "2") (pinfunction "2_2") (pintype "passive"))
      (node (ref "U2") (pin "8") (pinfunction "PC14-OSC32_IN_8") (pintype "passive"))
      (node (ref "Y1") (pin "2") (pinfunction "OSC2_2") (pintype "passive"))
    )
    (net (code "113") (name "Net-(U2-PC15-OSC32_OUT)") (class "Default")
      (node (ref "C4") (pin "2") (pinfunction "2_2") (pintype "passive"))
      (node (ref "U2") (pin "9") (pinfunction "PC15-OSC32_OUT_9") (pintype "passive"))
      (node (ref "Y1") (pin "1") (pinfunction "OSC1_1") (pintype "passive"))
    )
    (net (code "114") (name "Net-(U8-X1)") (class "Default")
      (node (ref "U8") (pin "1") (pinfunction "X1_1") (pintype "input"))
      (node (ref "Y3") (pin "2") (pinfunction "2_2") (pintype "passive"))
    )
    (net (code "115") (name "Net-(U8-X2)") (class "Default")
      (node (ref "U8") (pin "2") (pinfunction "X2_2") (pintype "input"))
      (node (ref "Y3") (pin "1") (pinfunction "1_1") (pintype "passive"))
    )
    (net (code "116") (name "Net-(U9-FB)") (class "Default")
      (node (ref "R30") (pin "1") (pinfunction "1_1") (pintype "passive"))
      (node (ref "R31") (pin "2") (pinfunction "2_2") (pintype "passive"))
      (node (ref "U9") (pin "5") (pinfunction "FB_5") (pintype "passive"))
    )
    (net (code "117") (name "Net-(U9-LX)") (class "Default")
      (node (ref "L2") (pin "2") (pinfunction "2_2") (pintype "passive"))
      (node (ref "U9") (pin "3") (pinfunction "LX_3") (pintype "passive"))
    )
    (net (code "118") (name "VBAT") (class "Default")
      (node (ref "BAT") (pin "1") (pinfunction "VCC_1") (pintype "passive"))
      (node (ref "D1") (pin "2") (pinfunction "K_2") (pintype "passive"))
      (node (ref "U2") (pin "6") (pinfunction "VBAT_6") (pintype "passive"))
      (node (ref "U8") (pin "3") (pinfunction "VBAT_3") (pintype "power_in"))
    )
    (net (code "119") (name "VCC3.3") (class "Default")
      (node (ref "C13") (pin "2") (pinfunction "2_2") (pintype "passive"))
      (node (ref "C14") (pin "2") (pinfunction "2_2") (pintype "passive"))
      (node (ref "C15") (pin "2") (pinfunction "2_2") (pintype "passive"))
      (node (ref "C16") (pin "2") (pinfunction "2_2") (pintype "passive"))
      (node (ref "C17") (pin "2") (pinfunction "2_2") (pintype "passive"))
      (node (ref "C18") (pin "2") (pinfunction "2_2") (pintype "passive"))
      (node (ref "C19") (pin "2") (pinfunction "2_2") (pintype "passive"))
      (node (ref "C20") (pin "2") (pinfunction "2_2") (pintype "passive"))
      (node (ref "C21") (pin "2") (pinfunction "2_2") (pintype "passive"))
      (node (ref "C22") (pin "2") (pinfunction "2_2") (pintype "passive"))
      (node (ref "C42") (pin "1") (pinfunction "1_1") (pintype "passive"))
      (node (ref "D1") (pin "1") (pinfunction "A_1") (pintype "passive"))
      (node (ref "P1") (pin "2") (pinfunction "2_2") (pintype "passive"))
      (node (ref "P2") (pin "2") (pinfunction "2_2") (pintype "passive"))
      (node (ref "P6") (pin "1") (pinfunction "1_1") (pintype "passive"))
      (node (ref "P7") (pin "1") (pinfunction "1_1") (pintype "passive"))
      (node (ref "P9") (pin "1") (pinfunction "1_1") (pintype "passive"))
      (node (ref "R13") (pin "2") (pinfunction "2_2") (pintype "passive"))
      (node (ref "R14") (pin "2") (pinfunction "2_2") (pintype "passive"))
      (node (ref "R17") (pin "1") (pinfunction "1_1") (pintype "passive"))
      (node (ref "R18") (pin "1") (pinfunction "1_1") (pintype "passive"))
      (node (ref "R19") (pin "1") (pinfunction "1_1") (pintype "passive"))
      (node (ref "R20") (pin "1") (pinfunction "1_1") (pintype "passive"))
      (node (ref "R22") (pin "1") (pinfunction "1_1") (pintype "passive"))
      (node (ref "R23") (pin "1") (pinfunction "1_1") (pintype "passive"))
      (node (ref "R27") (pin "2") (pinfunction "2_2") (pintype "passive"))
      (node (ref "R28") (pin "2") (pinfunction "2_2") (pintype "passive"))
      (node (ref "R32") (pin "1") (pinfunction "1_1") (pintype "passive"))
      (node (ref "TF1") (pin "4") (pinfunction "VCC_4") (pintype "passive"))
      (node (ref "U11") (pin "2") (pinfunction "Vout_2") (pintype "passive"))
      (node (ref "U2") (pin "108") (pinfunction "VDD_108") (pintype "passive"))
      (node (ref "U2") (pin "121") (pinfunction "VDD_121") (pintype "passive"))
      (node (ref "U2") (pin "131") (pinfunction "VDD_131") (pintype "passive"))
      (node (ref "U2") (pin "144") (pinfunction "VDD_144") (pintype "passive"))
      (node (ref "U2") (pin "17") (pinfunction "VDD_17") (pintype "passive"))
      (node (ref "U2") (pin "39") (pinfunction "VDD_39") (pintype "passive"))
      (node (ref "U2") (pin "52") (pinfunction "VDD_52") (pintype "passive"))
      (node (ref "U2") (pin "62") (pinfunction "VDD_62") (pintype "passive"))
      (node (ref "U2") (pin "72") (pinfunction "VDD_72") (pintype "passive"))
      (node (ref "U2") (pin "84") (pinfunction "VDD_84") (pintype "passive"))
      (node (ref "U2") (pin "95") (pinfunction "VDD_95") (pintype "passive"))
    )
    (net (code "120") (name "VCC5") (class "Default")
      (node (ref "BEEP1") (pin "1") (pinfunction "P_1") (pintype "passive"))
      (node (ref "D3") (pin "2") (pinfunction "K_2") (pintype "passive"))
    )
    (net (code "121") (name "VDDA") (class "Default")
      (node (ref "C7") (pin "2") (pinfunction "2_2") (pintype "passive"))
      (node (ref "C8") (pin "2") (pinfunction "2_2") (pintype "passive"))
      (node (ref "C9") (pin "2") (pinfunction "2_2") (pintype "passive"))
      (node (ref "R13") (pin "1") (pinfunction "1_1") (pintype "passive"))
      (node (ref "U2") (pin "32") (pinfunction "Vref+_32") (pintype "passive"))
      (node (ref "U2") (pin "33") (pinfunction "VDDA_33") (pintype "passive"))
    )
    (net (code "122") (name "WIFI_3.3") (class "Default")
      (node (ref "C10") (pin "2") (pinfunction "2_2") (pintype "passive"))
      (node (ref "C11") (pin "2") (pinfunction "2_2") (pintype "passive"))
      (node (ref "C32") (pin "1") (pinfunction "1_1") (pintype "passive"))
      (node (ref "U4") (pin "8") (pinfunction "VCC_8") (pintype "passive"))
      (node (ref "U7") (pin "2") (pinfunction "Vout_2") (pintype "passive"))
    )
    (net (code "123") (name "unconnected-(P3-VPP-Pad4)") (class "Default")
      (node (ref "P3") (pin "4") (pinfunction "VPP_4") (pintype "passive"))
    )
    (net (code "124") (name "unconnected-(P4-Pad6)") (class "Default")
      (node (ref "P4") (pin "6") (pinfunction "6_6") (pintype "passive"))
    )
    (net (code "125") (name "unconnected-(P4-Pad15)") (class "Default")
      (node (ref "P4") (pin "15") (pinfunction "15_15") (pintype "passive"))
    )
    (net (code "126") (name "unconnected-(P4-Pad16)") (class "Default")
      (node (ref "P4") (pin "16") (pinfunction "16_16") (pintype "passive"))
    )
    (net (code "127") (name "unconnected-(P6-Pad4)") (class "Default")
      (node (ref "P6") (pin "4") (pinfunction "4_4") (pintype "passive"))
    )
    (net (code "128") (name "unconnected-(P7-Pad4)") (class "Default")
      (node (ref "P7") (pin "4") (pinfunction "4_4") (pintype "passive"))
    )
    (net (code "129") (name "unconnected-(P8-Pad2)") (class "Default")
      (node (ref "P8") (pin "2") (pinfunction "2_2") (pintype "power_in"))
    )
    (net (code "130") (name "unconnected-(TF1-CD-Pad9)") (class "Default")
      (node (ref "TF1") (pin "9") (pinfunction "CD_9") (pintype "passive"))
    )
    (net (code "131") (name "unconnected-(TF1-NC-Pad10)") (class "Default")
      (node (ref "TF1") (pin "10") (pinfunction "NC_10") (pintype "passive"))
    )
    (net (code "132") (name "unconnected-(U1A-I2C2_SCL{slash}IO19-Pad1)") (class "Default")
      (node (ref "U1") (pin "1") (pinfunction "I2C2_SCL/IO19_1") (pintype "passive"))
    )
    (net (code "133") (name "unconnected-(U1A-I2C2_SDA{slash}IO20-Pad2)") (class "Default")
      (node (ref "U1") (pin "2") (pinfunction "I2C2_SDA/IO20_2") (pintype "passive"))
    )
    (net (code "134") (name "unconnected-(U1A-SD_CLK{slash}SPI1_CLK{slash}I2C1_SCL{slash}IO8-Pad8)") (class "Default")
      (node (ref "U1") (pin "8") (pinfunction "SD_CLK/SPI1_CLK/I2C1_SCL/IO8_8") (pintype "passive"))
    )
    (net (code "135") (name "unconnected-(U1A-SD_CMD{slash}SPI1_CS0{slash}I2C1_SDA{slash}IO9-Pad7)") (class "Default")
      (node (ref "U1") (pin "7") (pinfunction "SD_CMD/SPI1_CS0/I2C1_SDA/IO9_7") (pintype "passive"))
    )
    (net (code "136") (name "unconnected-(U1A-SD_D0{slash}SPI1_CS1{slash}IO10-Pad6)") (class "Default")
      (node (ref "U1") (pin "6") (pinfunction "SD_D0/SPI1_CS1/IO10_6") (pintype "passive"))
    )
    (net (code "137") (name "unconnected-(U1A-SD_D1{slash}SPI1_DO{slash}IO11-Pad5)") (class "Default")
      (node (ref "U1") (pin "5") (pinfunction "SD_D1/SPI1_DO/IO11_5") (pintype "passive"))
    )
    (net (code "138") (name "unconnected-(U1A-SD_D2{slash}SPI1_DI{slash}IO12-Pad4)") (class "Default")
      (node (ref "U1") (pin "4") (pinfunction "SD_D2/SPI1_DI/IO12_4") (pintype "passive"))
    )
    (net (code "139") (name "unconnected-(U1A-SD_D3{slash}IO13-Pad3)") (class "Default")
      (node (ref "U1") (pin "3") (pinfunction "SD_D3/IO13_3") (pintype "passive"))
    )
    (net (code "140") (name "unconnected-(U1A-SPK_N-Pad14)") (class "Default")
      (node (ref "U1") (pin "14") (pinfunction "SPK_N_14") (pintype "passive"))
    )
    (net (code "141") (name "unconnected-(U1A-SPK_P-Pad13)") (class "Default")
      (node (ref "U1") (pin "13") (pinfunction "SPK_P_13") (pintype "passive"))
    )
    (net (code "142") (name "unconnected-(U1B-ADC0-Pad15)") (class "Default")
      (node (ref "U1") (pin "15") (pinfunction "ADC0_15") (pintype "passive"))
    )
    (net (code "143") (name "unconnected-(U1B-ADC1-Pad16)") (class "Default")
      (node (ref "U1") (pin "16") (pinfunction "ADC1_16") (pintype "passive"))
    )
    (net (code "144") (name "unconnected-(U1B-IO26-Pad25)") (class "Default")
      (node (ref "U1") (pin "25") (pinfunction "IO26_25") (pintype "passive"))
    )
    (net (code "145") (name "unconnected-(U1B-LCD_CS{slash}I2S_LRCK{slash}IO15-Pad19)") (class "Default")
      (node (ref "U1") (pin "19") (pinfunction "LCD_CS/I2S_LRCK/IO15_19") (pintype "passive"))
    )
    (net (code "146") (name "unconnected-(U1B-LCD_DC{slash}IO18-Pad22)") (class "Default")
      (node (ref "U1") (pin "22") (pinfunction "LCD_DC/IO18_22") (pintype "passive"))
    )
    (net (code "147") (name "unconnected-(U1B-LCD_DIO{slash}I2S_DO{slash}IO17-Pad21)") (class "Default")
      (node (ref "U1") (pin "21") (pinfunction "LCD_DIO/I2S_DO/IO17_21") (pintype "passive"))
    )
    (net (code "148") (name "unconnected-(U1B-LCD_RSTB{slash}I2S_BCK{slash}IO14-Pad20)") (class "Default")
      (node (ref "U1") (pin "20") (pinfunction "LCD_RSTB/I2S_BCK/IO14_20") (pintype "passive"))
    )
    (net (code "149") (name "unconnected-(U1B-LCD_SCK{slash}I2S_DI{slash}IO16-Pad23)") (class "Default")
      (node (ref "U1") (pin "23") (pinfunction "LCD_SCK/I2S_DI/IO16_23") (pintype "passive"))
    )
    (net (code "150") (name "unconnected-(U1C-GPS_RF-Pad28)") (class "Default")
      (node (ref "U1") (pin "28") (pinfunction "GPS_RF_28") (pintype "passive"))
    )
    (net (code "151") (name "unconnected-(U1C-HST_RXD-Pad38)") (class "Default")
      (node (ref "U1") (pin "38") (pinfunction "HST_RXD_38") (pintype "passive"))
    )
    (net (code "152") (name "unconnected-(U1C-HST_TXD-Pad37)") (class "Default")
      (node (ref "U1") (pin "37") (pinfunction "HST_TXD_37") (pintype "passive"))
    )
    (net (code "153") (name "unconnected-(U1C-IO25-Pad32)") (class "Default")
      (node (ref "U1") (pin "32") (pinfunction "IO25_32") (pintype "passive"))
    )
    (net (code "154") (name "unconnected-(U1C-IO28-Pad30)") (class "Default")
      (node (ref "U1") (pin "30") (pinfunction "IO28_30") (pintype "passive"))
    )
    (net (code "155") (name "unconnected-(U1C-IO30-Pad31)") (class "Default")
      (node (ref "U1") (pin "31") (pinfunction "IO30_31") (pintype "passive"))
    )
    (net (code "156") (name "unconnected-(U1C-MIC_N-Pad33)") (class "Default")
      (node (ref "U1") (pin "33") (pinfunction "MIC_N_33") (pintype "passive"))
    )
    (net (code "157") (name "unconnected-(U1C-MIC_P-Pad34)") (class "Default")
      (node (ref "U1") (pin "34") (pinfunction "MIC_P_34") (pintype "passive"))
    )
    (net (code "158") (name "unconnected-(U1C-USB_N-Pad35)") (class "Default")
      (node (ref "U1") (pin "35") (pinfunction "USB_N_35") (pintype "passive"))
    )
    (net (code "159") (name "unconnected-(U1C-USB_P-Pad36)") (class "Default")
      (node (ref "U1") (pin "36") (pinfunction "USB_P_36") (pintype "passive"))
    )
    (net (code "160") (name "unconnected-(U1D-UART1_CTS{slash}IO2-Pad52)") (class "Default")
      (node (ref "U1") (pin "52") (pinfunction "UART1_CTS/IO2_52") (pintype "passive"))
    )
    (net (code "161") (name "unconnected-(U1D-UART1_RTS{slash}IO3-Pad51)") (class "Default")
      (node (ref "U1") (pin "51") (pinfunction "UART1_RTS/IO3_51") (pintype "passive"))
    )
    (net (code "162") (name "unconnected-(U1D-UART2_CTS{slash}I2C3_SCL{slash}IO6-Pad48)") (class "Default")
      (node (ref "U1") (pin "48") (pinfunction "UART2_CTS/I2C3_SCL/IO6_48") (pintype "passive"))
    )
    (net (code "163") (name "unconnected-(U1D-UART2_RTS{slash}I2C3_SDA{slash}IO7-Pad47)") (class "Default")
      (node (ref "U1") (pin "47") (pinfunction "UART2_RTS/I2C3_SDA/IO7_47") (pintype "passive"))
    )
    (net (code "164") (name "unconnected-(U1D-UART2_RXD{slash}IO4-Pad49)") (class "Default")
      (node (ref "U1") (pin "49") (pinfunction "UART2_RXD/IO4_49") (pintype "passive"))
    )
    (net (code "165") (name "unconnected-(U1D-UART2_TXD{slash}IO5-Pad50)") (class "Default")
      (node (ref "U1") (pin "50") (pinfunction "UART2_TXD/IO5_50") (pintype "passive"))
    )
    (net (code "166") (name "unconnected-(U2-NC-Pad106)") (class "Default")
      (node (ref "U2") (pin "106") (pinfunction "NC_106") (pintype "passive"))
    )
    (net (code "167") (name "unconnected-(U2-PA0-WKUP{slash}USART2_CTS{slash}ADC123_IN0{slash}TIM5_CH1{slash}TIM2_CH1_ETR{slash}TIM8_ETR-Pad34)") (class "Default")
      (node (ref "U2") (pin "34") (pinfunction "PA0-WKUP/USART2_CTS/ADC123_IN0/TIM5_CH1/TIM2_CH1_ETR/TIM8_ETR_34") (pintype "passive"))
    )
    (net (code "168") (name "unconnected-(U2-PA1{slash}USART2_RTS{slash}ADC123_IN1{slash}TIM5_CH2{slash}TIM2_CH2-Pad35)") (class "Default")
      (node (ref "U2") (pin "35") (pinfunction "PA1/USART2_RTS/ADC123_IN1/TIM5_CH2/TIM2_CH2_35") (pintype "passive"))
    )
    (net (code "169") (name "unconnected-(U2-PA4{slash}SPI1_NSS{slash}DAC_OUT1{slash}USART2_CK{slash}ADC12_IN4-Pad40)") (class "Default")
      (node (ref "U2") (pin "40") (pinfunction "PA4/SPI1_NSS/DAC_OUT1/USART2_CK/ADC12_IN4_40") (pintype "passive"))
    )
    (net (code "170") (name "unconnected-(U2-PA5{slash}SPI1_SCK{slash}DAC_OUT2{slash}ADC12_IN5-Pad41)") (class "Default")
      (node (ref "U2") (pin "41") (pinfunction "PA5/SPI1_SCK/DAC_OUT2/ADC12_IN5_41") (pintype "passive"))
    )
    (net (code "171") (name "unconnected-(U2-PA7{slash}SPI1_MOSI{slash}TIM8_CH1N{slash}ADC12_IN7{slash}TIM3_CH2-Pad43)") (class "Default")
      (node (ref "U2") (pin "43") (pinfunction "PA7/SPI1_MOSI/TIM8_CH1N/ADC12_IN7/TIM3_CH2_43") (pintype "passive"))
    )
    (net (code "172") (name "unconnected-(U2-PA11{slash}USART1_CTS{slash}CAN_RX{slash}TIM1_CH4{slash}USBDM-Pad103)") (class "Default")
      (node (ref "U2") (pin "103") (pinfunction "PA11/USART1_CTS/CAN_RX/TIM1_CH4/USBDM_103") (pintype "passive"))
    )
    (net (code "173") (name "unconnected-(U2-PA12{slash}USART1_RTS{slash}CAN_TX{slash}TIM1_ETR{slash}USBDP-Pad104)") (class "Default")
      (node (ref "U2") (pin "104") (pinfunction "PA12/USART1_RTS/CAN_TX/TIM1_ETR/USBDP_104") (pintype "passive"))
    )
    (net (code "174") (name "unconnected-(U2-PA15{slash}JTDI{slash}SPI3_NSS{slash}I2S3_WS-Pad110)") (class "Default")
      (node (ref "U2") (pin "110") (pinfunction "PA15/JTDI/SPI3_NSS/I2S3_WS_110") (pintype "passive"))
    )
    (net (code "175") (name "unconnected-(U2-PB7{slash}I2C1_SDA{slash}FSMC_NADV{slash}TIM4_CH2-Pad137)") (class "Default")
      (node (ref "U2") (pin "137") (pinfunction "PB7/I2C1_SDA/FSMC_NADV/TIM4_CH2_137") (pintype "passive"))
    )
    (net (code "176") (name "unconnected-(U2-PB12{slash}SPI2_NSS{slash}I2S2_WS{slash}I2C2_SMBAI{slash}USART3_CK{slash}TIM1BKIN-Pad73)") (class "Default")
      (node (ref "U2") (pin "73") (pinfunction "PB12/SPI2_NSS/I2S2_WS/I2C2_SMBAI/USART3_CK/TIM1BKIN_73") (pintype "passive"))
    )
    (net (code "177") (name "unconnected-(U2-PC13-TAMPER-RTC-Pad7)") (class "Default")
      (node (ref "U2") (pin "7") (pinfunction "PC13-TAMPER-RTC_7") (pintype "passive"))
    )
    (net (code "178") (name "unconnected-(U2-PD7{slash}FSMC_NE1{slash}FSMC_NCE2-Pad123)") (class "Default")
      (node (ref "U2") (pin "123") (pinfunction "PD7/FSMC_NE1/FSMC_NCE2_123") (pintype "passive"))
    )
    (net (code "179") (name "unconnected-(U2-PD11{slash}FSMC_A16-Pad80)") (class "Default")
      (node (ref "U2") (pin "80") (pinfunction "PD11/FSMC_A16_80") (pintype "passive"))
    )
    (net (code "180") (name "unconnected-(U2-PD12{slash}FSMC_A17-Pad81)") (class "Default")
      (node (ref "U2") (pin "81") (pinfunction "PD12/FSMC_A17_81") (pintype "passive"))
    )
    (net (code "181") (name "unconnected-(U2-PD13{slash}FSMC_A18-Pad82)") (class "Default")
      (node (ref "U2") (pin "82") (pinfunction "PD13/FSMC_A18_82") (pintype "passive"))
    )
    (net (code "182") (name "unconnected-(U2-PE0{slash}TIM4_ETR{slash}FSMC_NBL0-Pad141)") (class "Default")
      (node (ref "U2") (pin "141") (pinfunction "PE0/TIM4_ETR/FSMC_NBL0_141") (pintype "passive"))
    )
    (net (code "183") (name "unconnected-(U2-PE1{slash}FSMC_NBL1-Pad142)") (class "Default")
      (node (ref "U2") (pin "142") (pinfunction "PE1/FSMC_NBL1_142") (pintype "passive"))
    )
    (net (code "184") (name "unconnected-(U2-PE3{slash}TRACED0{slash}FSMC_A19-Pad2)") (class "Default")
      (node (ref "U2") (pin "2") (pinfunction "PE3/TRACED0/FSMC_A19_2") (pintype "passive"))
    )
    (net (code "185") (name "unconnected-(U2-PE4{slash}TRACED1{slash}FSMC_A20-Pad3)") (class "Default")
      (node (ref "U2") (pin "3") (pinfunction "PE4/TRACED1/FSMC_A20_3") (pintype "passive"))
    )
    (net (code "186") (name "unconnected-(U2-PE5{slash}TRACED2{slash}FSMC_A21-Pad4)") (class "Default")
      (node (ref "U2") (pin "4") (pinfunction "PE5/TRACED2/FSMC_A21_4") (pintype "passive"))
    )
    (net (code "187") (name "unconnected-(U2-PF1{slash}FSMC_A1-Pad11)") (class "Default")
      (node (ref "U2") (pin "11") (pinfunction "PF1/FSMC_A1_11") (pintype "passive"))
    )
    (net (code "188") (name "unconnected-(U2-PF2{slash}FSMC_A2-Pad12)") (class "Default")
      (node (ref "U2") (pin "12") (pinfunction "PF2/FSMC_A2_12") (pintype "passive"))
    )
    (net (code "189") (name "unconnected-(U2-PF3{slash}FSMC_A3-Pad13)") (class "Default")
      (node (ref "U2") (pin "13") (pinfunction "PF3/FSMC_A3_13") (pintype "passive"))
    )
    (net (code "190") (name "unconnected-(U2-PF4{slash}FSMC_A4-Pad14)") (class "Default")
      (node (ref "U2") (pin "14") (pinfunction "PF4/FSMC_A4_14") (pintype "passive"))
    )
    (net (code "191") (name "unconnected-(U2-PF5{slash}FSMC_A5-Pad15)") (class "Default")
      (node (ref "U2") (pin "15") (pinfunction "PF5/FSMC_A5_15") (pintype "passive"))
    )
    (net (code "192") (name "unconnected-(U2-PF6{slash}ADC3_IN4{slash}FSMC_NIORD-Pad18)") (class "Default")
      (node (ref "U2") (pin "18") (pinfunction "PF6/ADC3_IN4/FSMC_NIORD_18") (pintype "passive"))
    )
    (net (code "193") (name "unconnected-(U2-PF7{slash}ADC3_IN5{slash}FSMC_NREG-Pad19)") (class "Default")
      (node (ref "U2") (pin "19") (pinfunction "PF7/ADC3_IN5/FSMC_NREG_19") (pintype "passive"))
    )
    (net (code "194") (name "unconnected-(U2-PF8{slash}ADC3_IN6{slash}FSMC_NIOWR-Pad20)") (class "Default")
      (node (ref "U2") (pin "20") (pinfunction "PF8/ADC3_IN6/FSMC_NIOWR_20") (pintype "passive"))
    )
    (net (code "195") (name "unconnected-(U2-PF9{slash}ADC3_IN7{slash}FSMC_CD-Pad21)") (class "Default")
      (node (ref "U2") (pin "21") (pinfunction "PF9/ADC3_IN7/FSMC_CD_21") (pintype "passive"))
    )
    (net (code "196") (name "unconnected-(U2-PG5{slash}FSMC_A15-Pad90)") (class "Default")
      (node (ref "U2") (pin "90") (pinfunction "PG5/FSMC_A15_90") (pintype "passive"))
    )
    (net (code "197") (name "unconnected-(U2-PG10{slash}FSMC_NCE4_1{slash}FSMC_NE3-Pad125)") (class "Default")
      (node (ref "U2") (pin "125") (pinfunction "PG10/FSMC_NCE4_1/FSMC_NE3_125") (pintype "passive"))
    )
    (net (code "198") (name "unconnected-(U3-EC-CS-Pad30)") (class "Default")
      (node (ref "U3") (pin "30") (pinfunction "EC-CS_30") (pintype "passive"))
    )
    (net (code "199") (name "unconnected-(U3-NC-Pad28)") (class "Default")
      (node (ref "U3") (pin "28") (pinfunction "NC_28") (pintype "passive"))
    )
    (net (code "200") (name "unconnected-(U3-SD_CS-Pad32)") (class "Default")
      (node (ref "U3") (pin "32") (pinfunction "SD_CS_32") (pintype "passive"))
    )
    (net (code "201") (name "unconnected-(U4-ADC-Pad2)") (class "Default")
      (node (ref "U4") (pin "2") (pinfunction "ADC_2") (pintype "passive"))
    )
    (net (code "202") (name "unconnected-(U4-GND-Pad0)") (class "Default")
      (node (ref "U4") (pin "0") (pinfunction "GND_0") (pintype "passive"))
    )
    (net (code "203") (name "unconnected-(U4-GPIO0-Pad12)") (class "Default")
      (node (ref "U4") (pin "12") (pinfunction "GPIO0_12") (pintype "passive"))
    )
    (net (code "204") (name "unconnected-(U4-GPIO2-Pad11)") (class "Default")
      (node (ref "U4") (pin "11") (pinfunction "GPIO2_11") (pintype "passive"))
    )
    (net (code "205") (name "unconnected-(U4-GPIO4-Pad13)") (class "Default")
      (node (ref "U4") (pin "13") (pinfunction "GPIO4_13") (pintype "passive"))
    )
    (net (code "206") (name "unconnected-(U4-GPIO5-Pad14)") (class "Default")
      (node (ref "U4") (pin "14") (pinfunction "GPIO5_14") (pintype "passive"))
    )
    (net (code "207") (name "unconnected-(U4-GPIO12-Pad6)") (class "Default")
      (node (ref "U4") (pin "6") (pinfunction "GPIO12_6") (pintype "passive"))
    )
    (net (code "208") (name "unconnected-(U4-GPIO13-Pad7)") (class "Default")
      (node (ref "U4") (pin "7") (pinfunction "GPIO13_7") (pintype "passive"))
    )
    (net (code "209") (name "unconnected-(U4-GPIO14-Pad5)") (class "Default")
      (node (ref "U4") (pin "5") (pinfunction "GPIO14_5") (pintype "passive"))
    )
    (net (code "210") (name "unconnected-(U4-GPIO15-Pad10)") (class "Default")
      (node (ref "U4") (pin "10") (pinfunction "GPIO15_10") (pintype "passive"))
    )
    (net (code "211") (name "unconnected-(U4-GPIO16-Pad4)") (class "Default")
      (node (ref "U4") (pin "4") (pinfunction "GPIO16_4") (pintype "passive"))
    )
    (net (code "212") (name "unconnected-(USB1-D+-Pad3)") (class "Default")
      (node (ref "USB1") (pin "3") (pinfunction "D+_3") (pintype "passive"))
    )
    (net (code "213") (name "unconnected-(USB1-D--Pad2)") (class "Default")
      (node (ref "USB1") (pin "2") (pinfunction "D-_2") (pintype "passive"))
    )
    (net (code "214") (name "unconnected-(USB1-ID-Pad4)") (class "Default")
      (node (ref "USB1") (pin "4") (pinfunction "ID_4") (pintype "passive"))
    )
  )
)
